# axiom_beta_interface_dummy_v0_13_r1_6.net
KiCad netlist of a schematic drawn in EAGLE
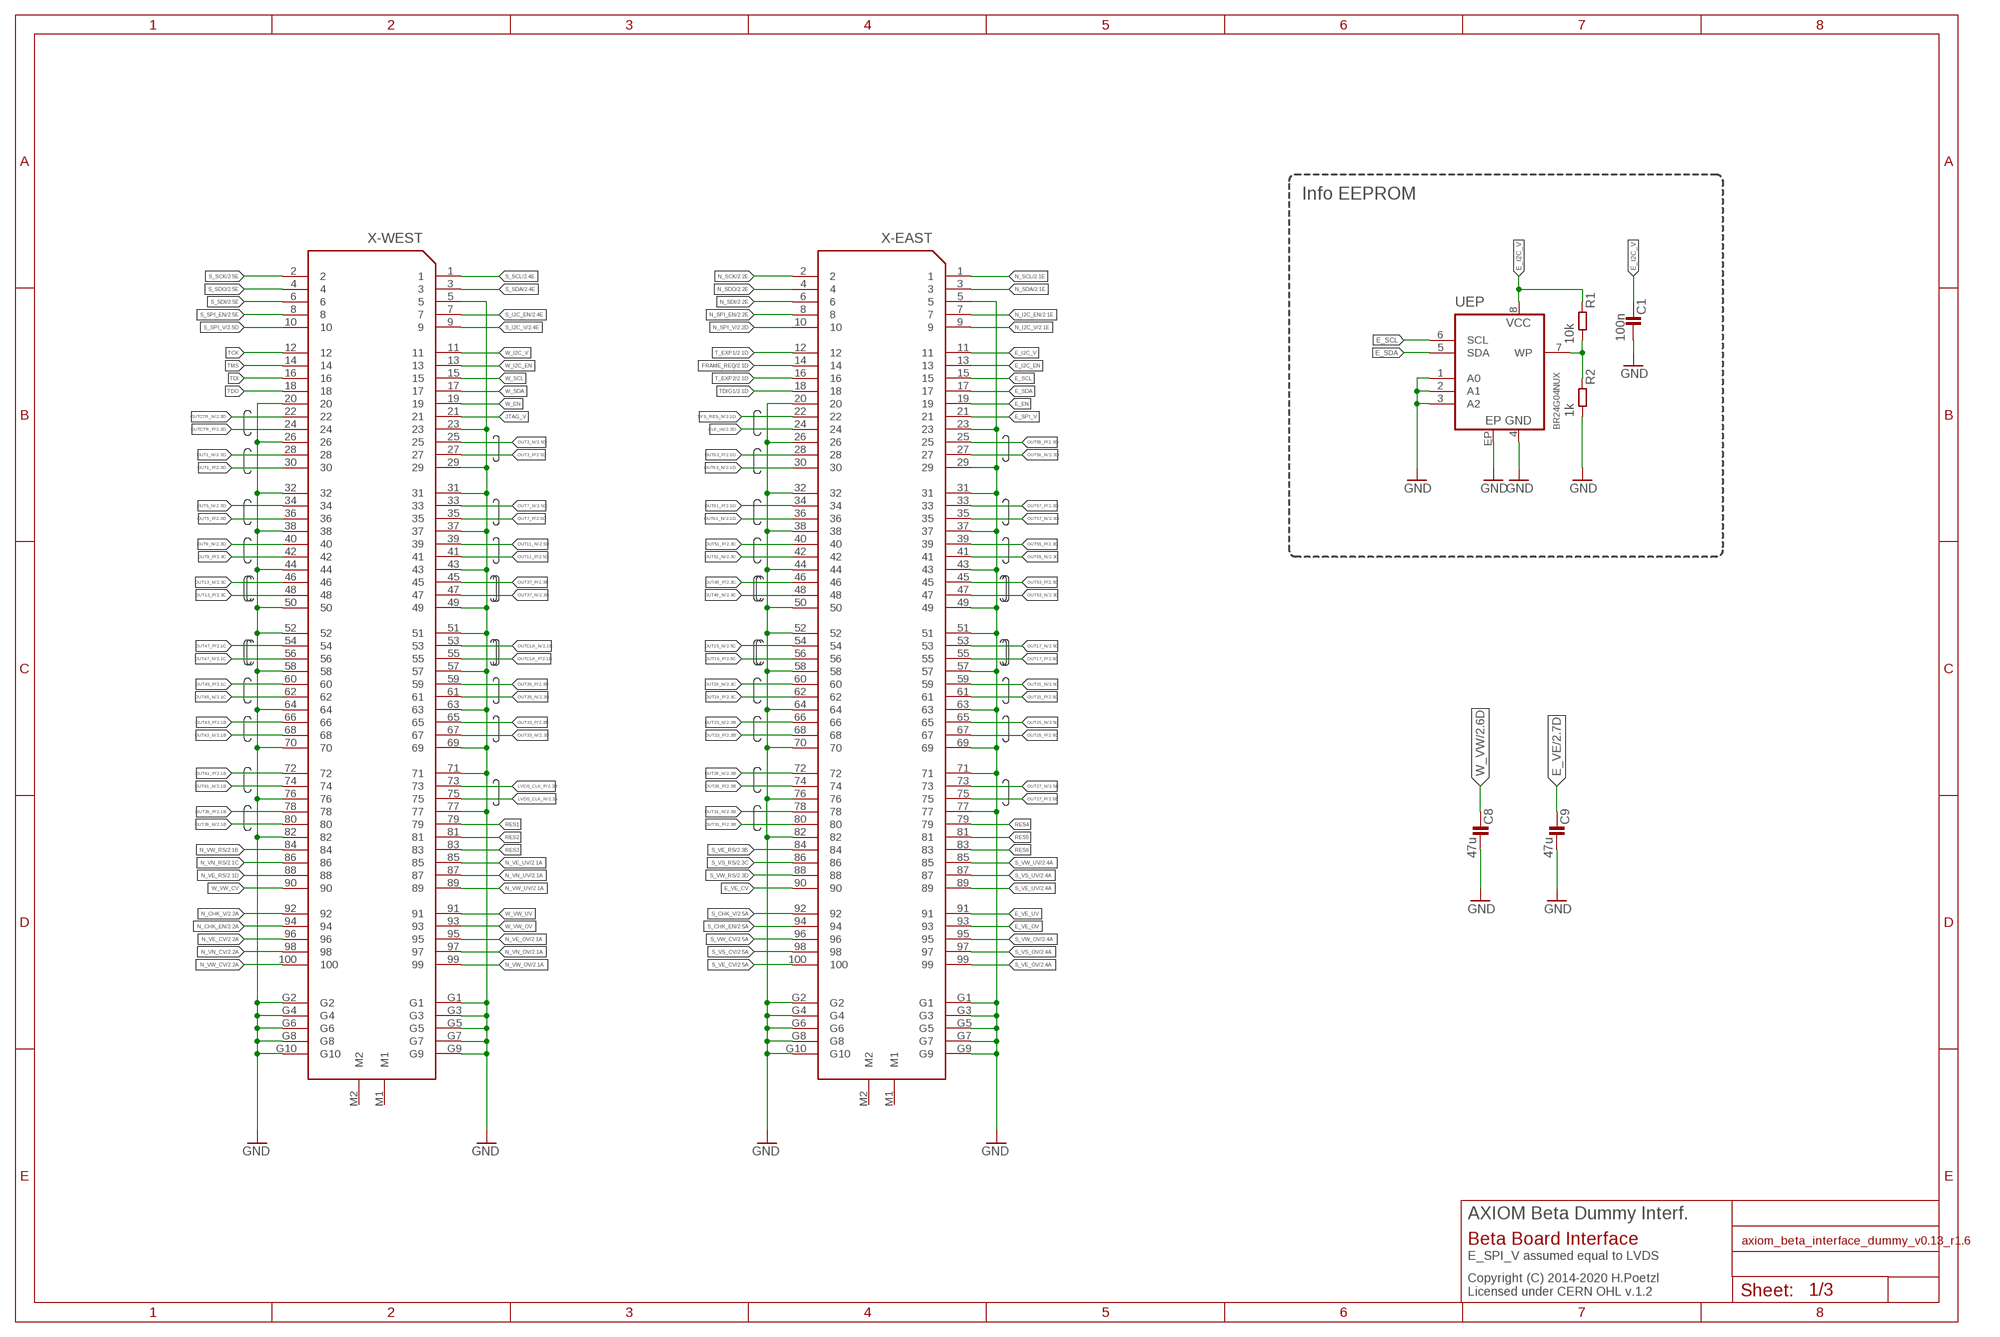
[diagram p0: schematic, sheet 1]
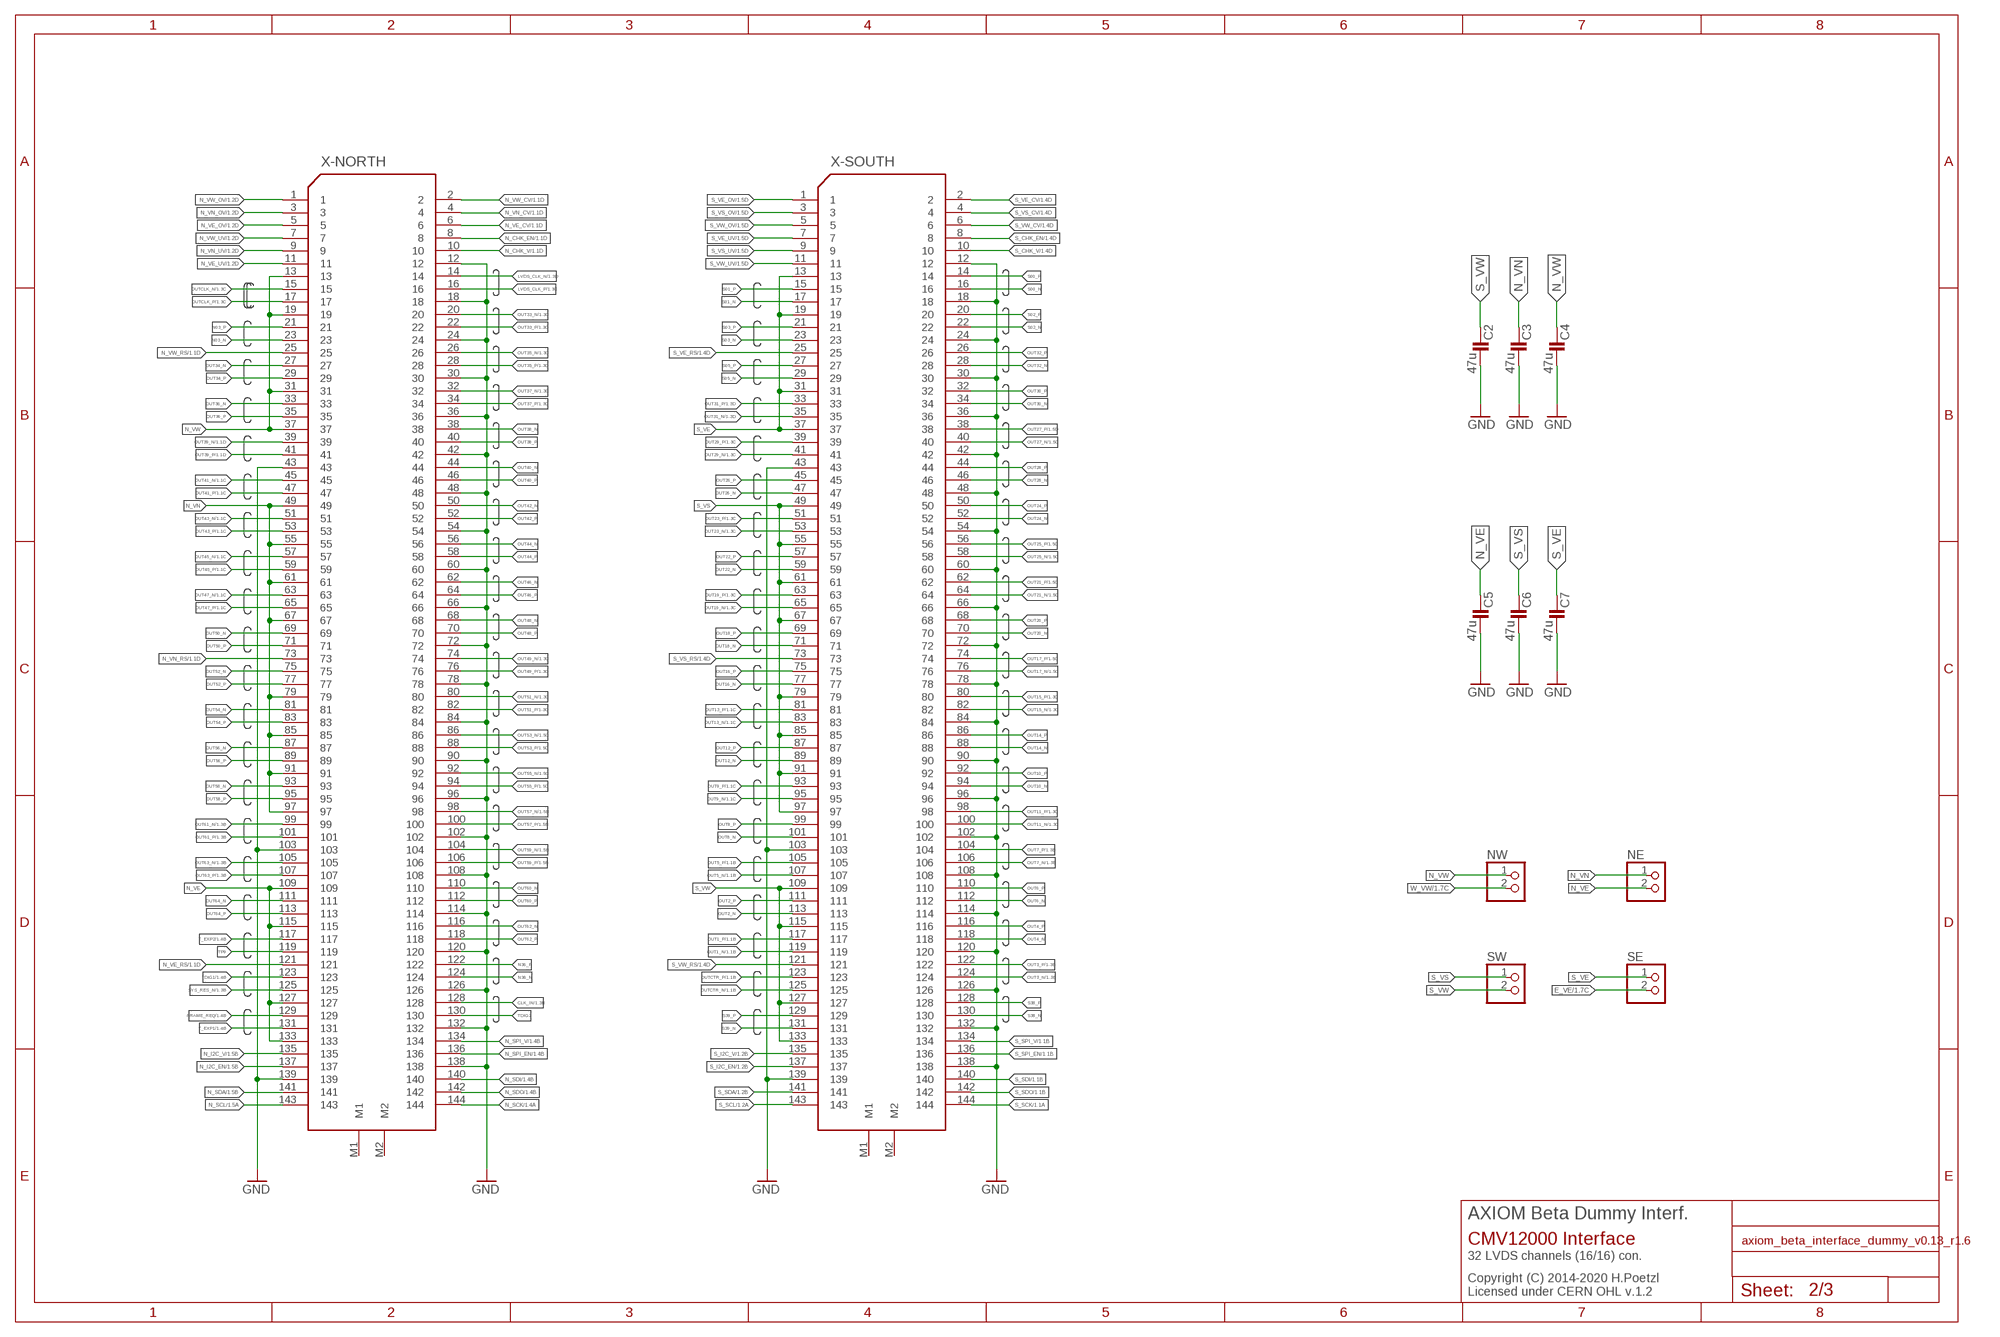
[diagram p1: schematic, sheet 2]
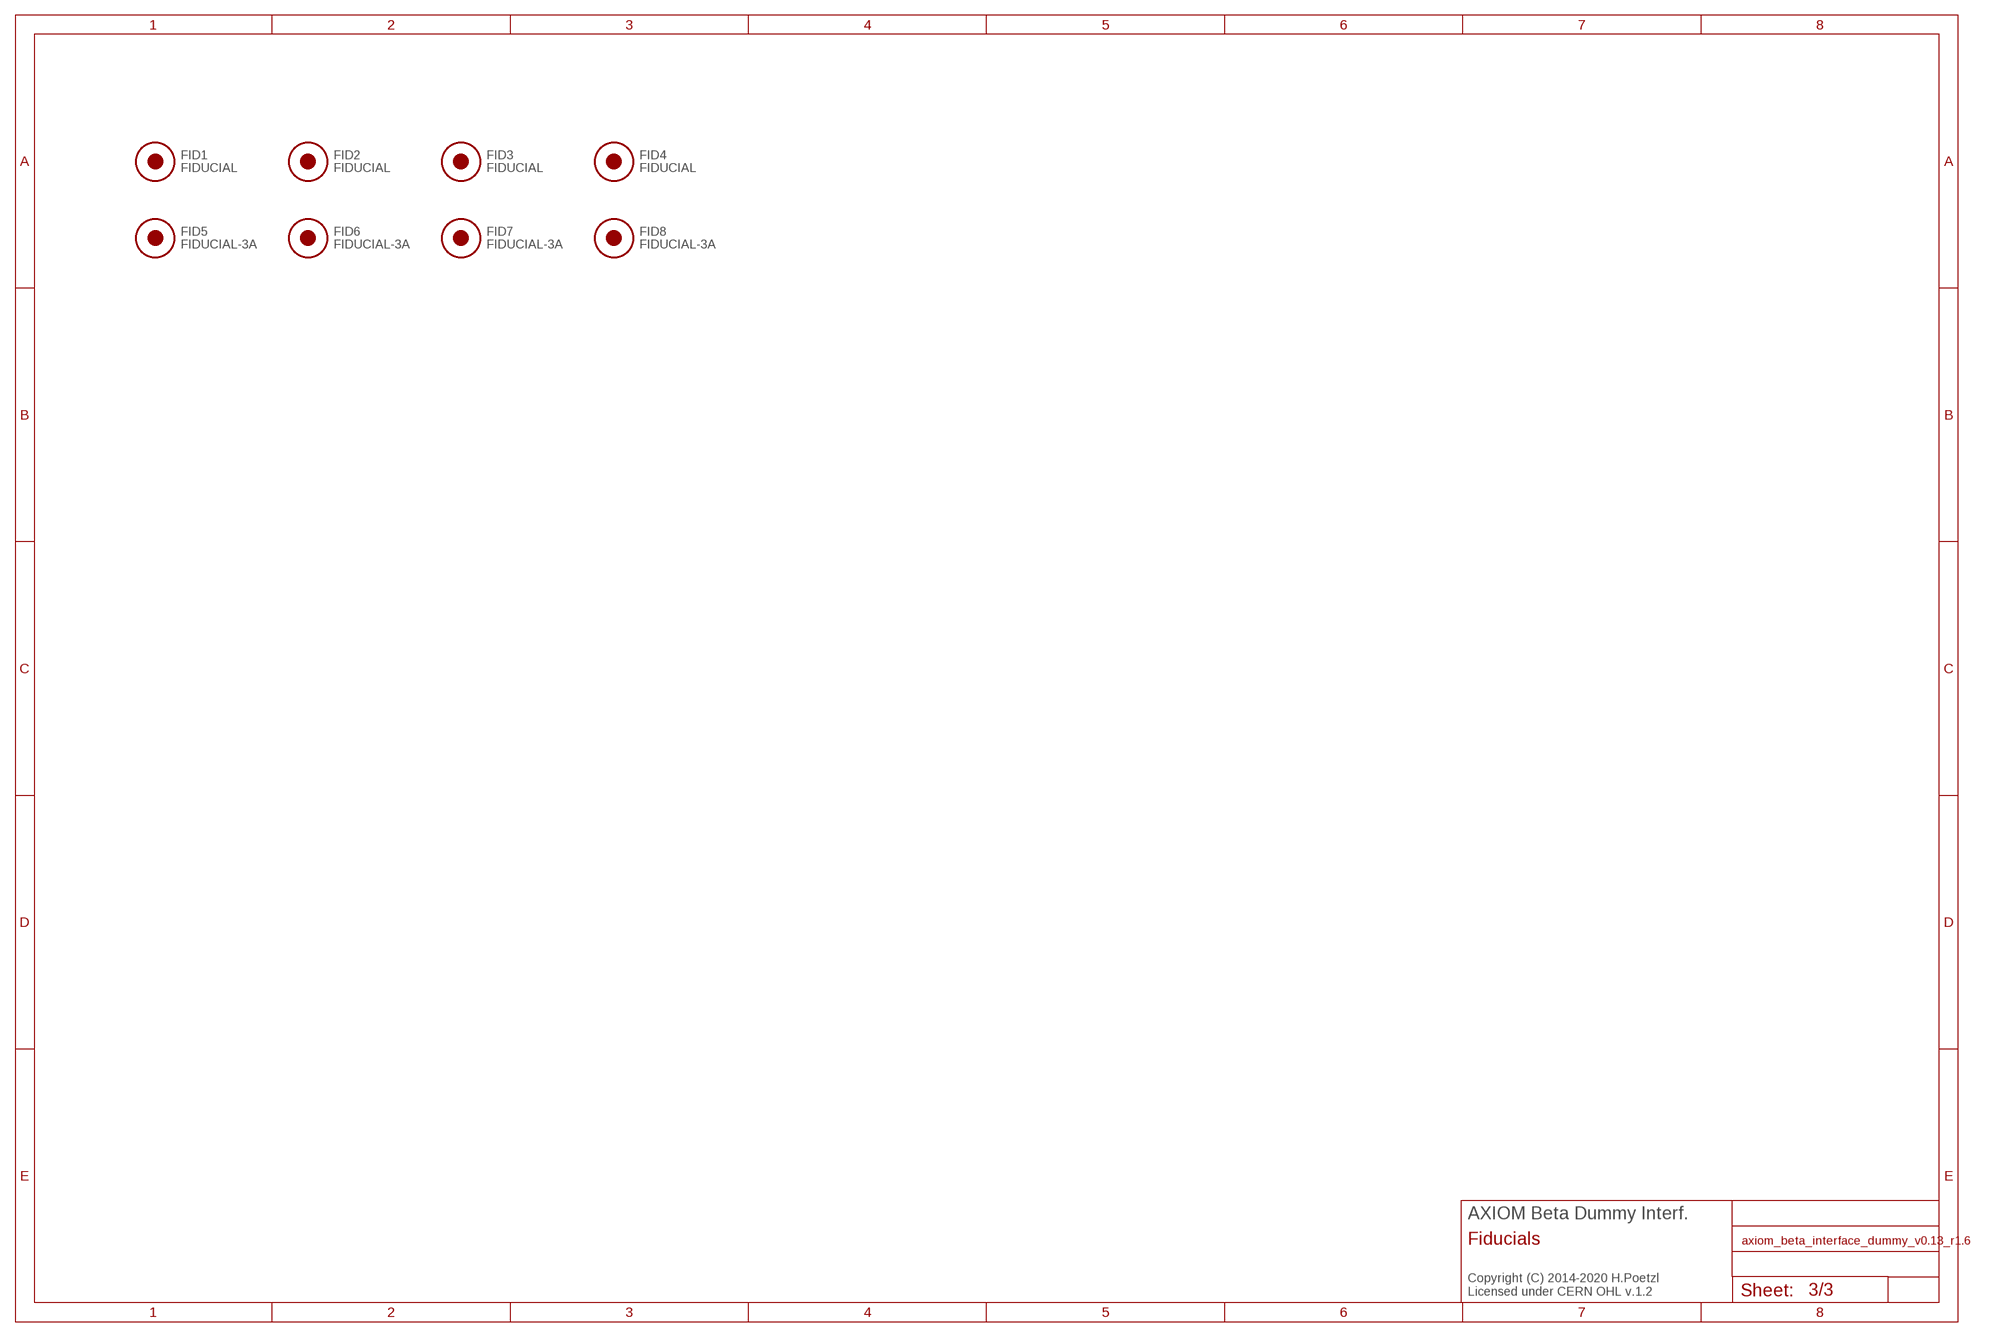
[diagram p2: schematic, sheet 3]

(export (version "E")
  (design (tool "Eeschema 10.0.6"))
  (components
    (comp (ref "C2")
      (value "47u")
      (footprint "eagle-import:0805-B")
      (libsource (lib "eagle-import") (part "C0805-B"))
    )
    (comp (ref "C3")
      (value "47u")
      (footprint "eagle-import:0805-B")
      (libsource (lib "eagle-import") (part "C0805-B"))
    )
    (comp (ref "C4")
      (value "47u")
      (footprint "eagle-import:0805-B")
      (libsource (lib "eagle-import") (part "C0805-B"))
    )
    (comp (ref "C5")
      (value "47u")
      (footprint "eagle-import:0805-B")
      (libsource (lib "eagle-import") (part "C0805-B"))
    )
    (comp (ref "C6")
      (value "47u")
      (footprint "eagle-import:0805-B")
      (libsource (lib "eagle-import") (part "C0805-B"))
    )
    (comp (ref "C7")
      (value "47u")
      (footprint "eagle-import:0805-B")
      (libsource (lib "eagle-import") (part "C0805-B"))
    )
    (comp (ref "NE")
      (value "PINHD-1X02_2.54")
      (footprint "eagle-import:1X02")
      (libsource (lib "eagle-import") (part "PINHD-1X02_2.54"))
    )
    (comp (ref "NW")
      (value "PINHD-1X02_2.54")
      (footprint "eagle-import:1X02")
      (libsource (lib "eagle-import") (part "PINHD-1X02_2.54"))
    )
    (comp (ref "SE")
      (value "PINHD-1X02_2.54")
      (footprint "eagle-import:1X02")
      (libsource (lib "eagle-import") (part "PINHD-1X02_2.54"))
    )
    (comp (ref "SW")
      (value "PINHD-1X02_2.54")
      (footprint "eagle-import:1X02")
      (libsource (lib "eagle-import") (part "PINHD-1X02_2.54"))
    )
    (comp (ref "X-NORTH")
      (value "FX10-144S")
      (footprint "eagle-import:FX10A-144S")
      (libsource (lib "eagle-import") (part "FX10-144S"))
    )
    (comp (ref "X-SOUTH")
      (value "FX10-144S")
      (footprint "eagle-import:FX10A-144S")
      (libsource (lib "eagle-import") (part "FX10-144S"))
    )
    (comp (ref "C1")
      (value "100n")
      (footprint "eagle-import:0402-B")
      (libsource (lib "eagle-import") (part "C0402-B"))
    )
    (comp (ref "C8")
      (value "47u")
      (footprint "eagle-import:0805-B")
      (libsource (lib "eagle-import") (part "C0805-B"))
    )
    (comp (ref "C9")
      (value "47u")
      (footprint "eagle-import:0805-B")
      (libsource (lib "eagle-import") (part "C0805-B"))
    )
    (comp (ref "R1")
      (value "10k")
      (footprint "eagle-import:0402-B")
      (libsource (lib "eagle-import") (part "R0402-B"))
    )
    (comp (ref "R2")
      (value "1k")
      (footprint "eagle-import:0402-B")
      (libsource (lib "eagle-import") (part "R0402-B"))
    )
    (comp (ref "UEP")
      (value "BR24G04NUX")
      (footprint "eagle-import:DFN200X300X100-9N")
      (libsource (lib "eagle-import") (part "BR24G04NUX"))
    )
    (comp (ref "X-EAST")
      (value "FX10-100/10P")
      (footprint "eagle-import:FX10A-100P_10")
      (libsource (lib "eagle-import") (part "FX10-100/10P"))
    )
    (comp (ref "X-WEST")
      (value "FX10-100/10P")
      (footprint "eagle-import:FX10A-100P_10")
      (libsource (lib "eagle-import") (part "FX10-100/10P"))
    )
    (comp (ref "FID1")
      (value "FIDUCIAL")
      (footprint "eagle-import:FID_ARROW")
      (libsource (lib "eagle-import") (part "FIDUCIAL"))
    )
    (comp (ref "FID2")
      (value "FIDUCIAL")
      (footprint "eagle-import:FID_ARROW")
      (libsource (lib "eagle-import") (part "FIDUCIAL"))
    )
    (comp (ref "FID3")
      (value "FIDUCIAL")
      (footprint "eagle-import:FID_ARROW")
      (libsource (lib "eagle-import") (part "FIDUCIAL"))
    )
    (comp (ref "FID4")
      (value "FIDUCIAL")
      (footprint "eagle-import:FID_ARROW")
      (libsource (lib "eagle-import") (part "FIDUCIAL"))
    )
    (comp (ref "FID5")
      (value "FIDUCIAL-3A")
      (footprint "eagle-import:FID_3ARROW")
      (libsource (lib "eagle-import") (part "FIDUCIAL-3A"))
    )
    (comp (ref "FID6")
      (value "FIDUCIAL-3A")
      (footprint "eagle-import:FID_3ARROW")
      (libsource (lib "eagle-import") (part "FIDUCIAL-3A"))
    )
    (comp (ref "FID7")
      (value "FIDUCIAL-3A")
      (footprint "eagle-import:FID_3ARROW")
      (libsource (lib "eagle-import") (part "FIDUCIAL-3A"))
    )
    (comp (ref "FID8")
      (value "FIDUCIAL-3A")
      (footprint "eagle-import:FID_3ARROW")
      (libsource (lib "eagle-import") (part "FIDUCIAL-3A"))
    )
  )
  (nets
    (net (code "1") (name "CLK_IN") (class "Default")
      (node (ref "X-EAST") (pin "24") (pinfunction "24_24") (pintype "bidirectional"))
      (node (ref "X-NORTH") (pin "128") (pinfunction "128_128") (pintype "bidirectional"))
    )
    (net (code "2") (name "E_EN") (class "Default")
      (node (ref "X-EAST") (pin "19") (pinfunction "19_19") (pintype "bidirectional"))
    )
    (net (code "3") (name "E_I2C_EN") (class "Default")
      (node (ref "X-EAST") (pin "13") (pinfunction "13_13") (pintype "bidirectional"))
    )
    (net (code "4") (name "E_I2C_V") (class "Default")
      (node (ref "C1") (pin "1") (pinfunction "1_1") (pintype "passive"))
      (node (ref "R1") (pin "1") (pinfunction "1_1") (pintype "passive"))
      (node (ref "UEP") (pin "8") (pinfunction "VCC_8") (pintype "power_in"))
      (node (ref "X-EAST") (pin "11") (pinfunction "11_11") (pintype "bidirectional"))
    )
    (net (code "5") (name "E_SCL") (class "Default")
      (node (ref "UEP") (pin "6") (pinfunction "SCL_6") (pintype "input"))
      (node (ref "X-EAST") (pin "15") (pinfunction "15_15") (pintype "bidirectional"))
    )
    (net (code "6") (name "E_SDA") (class "Default")
      (node (ref "UEP") (pin "5") (pinfunction "SDA_5") (pintype "bidirectional"))
      (node (ref "X-EAST") (pin "17") (pinfunction "17_17") (pintype "bidirectional"))
    )
    (net (code "7") (name "E_SPI_V") (class "Default")
      (node (ref "X-EAST") (pin "21") (pinfunction "21_21") (pintype "bidirectional"))
    )
    (net (code "8") (name "E_VE") (class "Default")
      (node (ref "C9") (pin "1") (pinfunction "1_1") (pintype "passive"))
      (node (ref "SE") (pin "2") (pinfunction "2_2") (pintype "passive"))
    )
    (net (code "9") (name "E_VE_CV") (class "Default")
      (node (ref "X-EAST") (pin "90") (pinfunction "90_90") (pintype "bidirectional"))
    )
    (net (code "10") (name "E_VE_OV") (class "Default")
      (node (ref "X-EAST") (pin "93") (pinfunction "93_93") (pintype "bidirectional"))
    )
    (net (code "11") (name "E_VE_UV") (class "Default")
      (node (ref "X-EAST") (pin "91") (pinfunction "91_91") (pintype "bidirectional"))
    )
    (net (code "12") (name "FRAME_REQ") (class "Default")
      (node (ref "X-EAST") (pin "14") (pinfunction "14_14") (pintype "bidirectional"))
      (node (ref "X-NORTH") (pin "129") (pinfunction "129_129") (pintype "bidirectional"))
    )
    (net (code "13") (name "GND") (class "Default")
      (node (ref "C1") (pin "2") (pinfunction "2_2") (pintype "passive"))
      (node (ref "C2") (pin "2") (pinfunction "2_2") (pintype "passive"))
      (node (ref "C3") (pin "2") (pinfunction "2_2") (pintype "passive"))
      (node (ref "C4") (pin "2") (pinfunction "2_2") (pintype "passive"))
      (node (ref "C5") (pin "2") (pinfunction "2_2") (pintype "passive"))
      (node (ref "C6") (pin "2") (pinfunction "2_2") (pintype "passive"))
      (node (ref "C7") (pin "2") (pinfunction "2_2") (pintype "passive"))
      (node (ref "C8") (pin "2") (pinfunction "2_2") (pintype "passive"))
      (node (ref "C9") (pin "2") (pinfunction "2_2") (pintype "passive"))
      (node (ref "R2") (pin "2") (pinfunction "2_2") (pintype "passive"))
      (node (ref "UEP") (pin "1") (pinfunction "A0_1") (pintype "input"))
      (node (ref "UEP") (pin "2") (pinfunction "A1_2") (pintype "input"))
      (node (ref "UEP") (pin "3") (pinfunction "A2_3") (pintype "input"))
      (node (ref "UEP") (pin "4") (pinfunction "GND_4") (pintype "passive"))
      (node (ref "UEP") (pin "EP") (pinfunction "EP_EP") (pintype "passive"))
      (node (ref "X-EAST") (pin "20") (pinfunction "20_20") (pintype "bidirectional"))
      (node (ref "X-EAST") (pin "23") (pinfunction "23_23") (pintype "bidirectional"))
      (node (ref "X-EAST") (pin "26") (pinfunction "26_26") (pintype "bidirectional"))
      (node (ref "X-EAST") (pin "29") (pinfunction "29_29") (pintype "bidirectional"))
      (node (ref "X-EAST") (pin "31") (pinfunction "31_31") (pintype "bidirectional"))
      (node (ref "X-EAST") (pin "32") (pinfunction "32_32") (pintype "bidirectional"))
      (node (ref "X-EAST") (pin "37") (pinfunction "37_37") (pintype "bidirectional"))
      (node (ref "X-EAST") (pin "38") (pinfunction "38_38") (pintype "bidirectional"))
      (node (ref "X-EAST") (pin "43") (pinfunction "43_43") (pintype "bidirectional"))
      (node (ref "X-EAST") (pin "44") (pinfunction "44_44") (pintype "bidirectional"))
      (node (ref "X-EAST") (pin "49") (pinfunction "49_49") (pintype "bidirectional"))
      (node (ref "X-EAST") (pin "5") (pinfunction "5_5") (pintype "bidirectional"))
      (node (ref "X-EAST") (pin "50") (pinfunction "50_50") (pintype "bidirectional"))
      (node (ref "X-EAST") (pin "51") (pinfunction "51_51") (pintype "bidirectional"))
      (node (ref "X-EAST") (pin "52") (pinfunction "52_52") (pintype "bidirectional"))
      (node (ref "X-EAST") (pin "57") (pinfunction "57_57") (pintype "bidirectional"))
      (node (ref "X-EAST") (pin "58") (pinfunction "58_58") (pintype "bidirectional"))
      (node (ref "X-EAST") (pin "63") (pinfunction "63_63") (pintype "bidirectional"))
      (node (ref "X-EAST") (pin "64") (pinfunction "64_64") (pintype "bidirectional"))
      (node (ref "X-EAST") (pin "69") (pinfunction "69_69") (pintype "bidirectional"))
      (node (ref "X-EAST") (pin "70") (pinfunction "70_70") (pintype "bidirectional"))
      (node (ref "X-EAST") (pin "71") (pinfunction "71_71") (pintype "bidirectional"))
      (node (ref "X-EAST") (pin "76") (pinfunction "76_76") (pintype "bidirectional"))
      (node (ref "X-EAST") (pin "77") (pinfunction "77_77") (pintype "bidirectional"))
      (node (ref "X-EAST") (pin "82") (pinfunction "82_82") (pintype "bidirectional"))
      (node (ref "X-EAST") (pin "G1") (pinfunction "G1_G1") (pintype "bidirectional"))
      (node (ref "X-EAST") (pin "G10") (pinfunction "G10_G10") (pintype "bidirectional"))
      (node (ref "X-EAST") (pin "G2") (pinfunction "G2_G2") (pintype "bidirectional"))
      (node (ref "X-EAST") (pin "G3") (pinfunction "G3_G3") (pintype "bidirectional"))
      (node (ref "X-EAST") (pin "G4") (pinfunction "G4_G4") (pintype "bidirectional"))
      (node (ref "X-EAST") (pin "G5") (pinfunction "G5_G5") (pintype "bidirectional"))
      (node (ref "X-EAST") (pin "G6") (pinfunction "G6_G6") (pintype "bidirectional"))
      (node (ref "X-EAST") (pin "G7") (pinfunction "G7_G7") (pintype "bidirectional"))
      (node (ref "X-EAST") (pin "G8") (pinfunction "G8_G8") (pintype "bidirectional"))
      (node (ref "X-EAST") (pin "G9") (pinfunction "G9_G9") (pintype "bidirectional"))
      (node (ref "X-NORTH") (pin "102") (pinfunction "102_102") (pintype "bidirectional"))
      (node (ref "X-NORTH") (pin "103") (pinfunction "103_103") (pintype "bidirectional"))
      (node (ref "X-NORTH") (pin "108") (pinfunction "108_108") (pintype "bidirectional"))
      (node (ref "X-NORTH") (pin "114") (pinfunction "114_114") (pintype "bidirectional"))
      (node (ref "X-NORTH") (pin "12") (pinfunction "12_12") (pintype "bidirectional"))
      (node (ref "X-NORTH") (pin "120") (pinfunction "120_120") (pintype "bidirectional"))
      (node (ref "X-NORTH") (pin "126") (pinfunction "126_126") (pintype "bidirectional"))
      (node (ref "X-NORTH") (pin "132") (pinfunction "132_132") (pintype "bidirectional"))
      (node (ref "X-NORTH") (pin "138") (pinfunction "138_138") (pintype "bidirectional"))
      (node (ref "X-NORTH") (pin "139") (pinfunction "139_139") (pintype "bidirectional"))
      (node (ref "X-NORTH") (pin "18") (pinfunction "18_18") (pintype "bidirectional"))
      (node (ref "X-NORTH") (pin "24") (pinfunction "24_24") (pintype "bidirectional"))
      (node (ref "X-NORTH") (pin "30") (pinfunction "30_30") (pintype "bidirectional"))
      (node (ref "X-NORTH") (pin "36") (pinfunction "36_36") (pintype "bidirectional"))
      (node (ref "X-NORTH") (pin "42") (pinfunction "42_42") (pintype "bidirectional"))
      (node (ref "X-NORTH") (pin "43") (pinfunction "43_43") (pintype "bidirectional"))
      (node (ref "X-NORTH") (pin "48") (pinfunction "48_48") (pintype "bidirectional"))
      (node (ref "X-NORTH") (pin "54") (pinfunction "54_54") (pintype "bidirectional"))
      (node (ref "X-NORTH") (pin "60") (pinfunction "60_60") (pintype "bidirectional"))
      (node (ref "X-NORTH") (pin "66") (pinfunction "66_66") (pintype "bidirectional"))
      (node (ref "X-NORTH") (pin "72") (pinfunction "72_72") (pintype "bidirectional"))
      (node (ref "X-NORTH") (pin "78") (pinfunction "78_78") (pintype "bidirectional"))
      (node (ref "X-NORTH") (pin "84") (pinfunction "84_84") (pintype "bidirectional"))
      (node (ref "X-NORTH") (pin "90") (pinfunction "90_90") (pintype "bidirectional"))
      (node (ref "X-NORTH") (pin "96") (pinfunction "96_96") (pintype "bidirectional"))
      (node (ref "X-SOUTH") (pin "102") (pinfunction "102_102") (pintype "bidirectional"))
      (node (ref "X-SOUTH") (pin "103") (pinfunction "103_103") (pintype "bidirectional"))
      (node (ref "X-SOUTH") (pin "108") (pinfunction "108_108") (pintype "bidirectional"))
      (node (ref "X-SOUTH") (pin "114") (pinfunction "114_114") (pintype "bidirectional"))
      (node (ref "X-SOUTH") (pin "12") (pinfunction "12_12") (pintype "bidirectional"))
      (node (ref "X-SOUTH") (pin "120") (pinfunction "120_120") (pintype "bidirectional"))
      (node (ref "X-SOUTH") (pin "126") (pinfunction "126_126") (pintype "bidirectional"))
      (node (ref "X-SOUTH") (pin "132") (pinfunction "132_132") (pintype "bidirectional"))
      (node (ref "X-SOUTH") (pin "138") (pinfunction "138_138") (pintype "bidirectional"))
      (node (ref "X-SOUTH") (pin "139") (pinfunction "139_139") (pintype "bidirectional"))
      (node (ref "X-SOUTH") (pin "18") (pinfunction "18_18") (pintype "bidirectional"))
      (node (ref "X-SOUTH") (pin "24") (pinfunction "24_24") (pintype "bidirectional"))
      (node (ref "X-SOUTH") (pin "30") (pinfunction "30_30") (pintype "bidirectional"))
      (node (ref "X-SOUTH") (pin "36") (pinfunction "36_36") (pintype "bidirectional"))
      (node (ref "X-SOUTH") (pin "42") (pinfunction "42_42") (pintype "bidirectional"))
      (node (ref "X-SOUTH") (pin "43") (pinfunction "43_43") (pintype "bidirectional"))
      (node (ref "X-SOUTH") (pin "48") (pinfunction "48_48") (pintype "bidirectional"))
      (node (ref "X-SOUTH") (pin "54") (pinfunction "54_54") (pintype "bidirectional"))
      (node (ref "X-SOUTH") (pin "60") (pinfunction "60_60") (pintype "bidirectional"))
      (node (ref "X-SOUTH") (pin "66") (pinfunction "66_66") (pintype "bidirectional"))
      (node (ref "X-SOUTH") (pin "72") (pinfunction "72_72") (pintype "bidirectional"))
      (node (ref "X-SOUTH") (pin "78") (pinfunction "78_78") (pintype "bidirectional"))
      (node (ref "X-SOUTH") (pin "84") (pinfunction "84_84") (pintype "bidirectional"))
      (node (ref "X-SOUTH") (pin "90") (pinfunction "90_90") (pintype "bidirectional"))
      (node (ref "X-SOUTH") (pin "96") (pinfunction "96_96") (pintype "bidirectional"))
      (node (ref "X-WEST") (pin "20") (pinfunction "20_20") (pintype "bidirectional"))
      (node (ref "X-WEST") (pin "23") (pinfunction "23_23") (pintype "bidirectional"))
      (node (ref "X-WEST") (pin "26") (pinfunction "26_26") (pintype "bidirectional"))
      (node (ref "X-WEST") (pin "29") (pinfunction "29_29") (pintype "bidirectional"))
      (node (ref "X-WEST") (pin "31") (pinfunction "31_31") (pintype "bidirectional"))
      (node (ref "X-WEST") (pin "32") (pinfunction "32_32") (pintype "bidirectional"))
      (node (ref "X-WEST") (pin "37") (pinfunction "37_37") (pintype "bidirectional"))
      (node (ref "X-WEST") (pin "38") (pinfunction "38_38") (pintype "bidirectional"))
      (node (ref "X-WEST") (pin "43") (pinfunction "43_43") (pintype "bidirectional"))
      (node (ref "X-WEST") (pin "44") (pinfunction "44_44") (pintype "bidirectional"))
      (node (ref "X-WEST") (pin "49") (pinfunction "49_49") (pintype "bidirectional"))
      (node (ref "X-WEST") (pin "5") (pinfunction "5_5") (pintype "bidirectional"))
      (node (ref "X-WEST") (pin "50") (pinfunction "50_50") (pintype "bidirectional"))
      (node (ref "X-WEST") (pin "51") (pinfunction "51_51") (pintype "bidirectional"))
      (node (ref "X-WEST") (pin "52") (pinfunction "52_52") (pintype "bidirectional"))
      (node (ref "X-WEST") (pin "57") (pinfunction "57_57") (pintype "bidirectional"))
      (node (ref "X-WEST") (pin "58") (pinfunction "58_58") (pintype "bidirectional"))
      (node (ref "X-WEST") (pin "63") (pinfunction "63_63") (pintype "bidirectional"))
      (node (ref "X-WEST") (pin "64") (pinfunction "64_64") (pintype "bidirectional"))
      (node (ref "X-WEST") (pin "69") (pinfunction "69_69") (pintype "bidirectional"))
      (node (ref "X-WEST") (pin "70") (pinfunction "70_70") (pintype "bidirectional"))
      (node (ref "X-WEST") (pin "71") (pinfunction "71_71") (pintype "bidirectional"))
      (node (ref "X-WEST") (pin "76") (pinfunction "76_76") (pintype "bidirectional"))
      (node (ref "X-WEST") (pin "77") (pinfunction "77_77") (pintype "bidirectional"))
      (node (ref "X-WEST") (pin "82") (pinfunction "82_82") (pintype "bidirectional"))
      (node (ref "X-WEST") (pin "G1") (pinfunction "G1_G1") (pintype "bidirectional"))
      (node (ref "X-WEST") (pin "G10") (pinfunction "G10_G10") (pintype "bidirectional"))
      (node (ref "X-WEST") (pin "G2") (pinfunction "G2_G2") (pintype "bidirectional"))
      (node (ref "X-WEST") (pin "G3") (pinfunction "G3_G3") (pintype "bidirectional"))
      (node (ref "X-WEST") (pin "G4") (pinfunction "G4_G4") (pintype "bidirectional"))
      (node (ref "X-WEST") (pin "G5") (pinfunction "G5_G5") (pintype "bidirectional"))
      (node (ref "X-WEST") (pin "G6") (pinfunction "G6_G6") (pintype "bidirectional"))
      (node (ref "X-WEST") (pin "G7") (pinfunction "G7_G7") (pintype "bidirectional"))
      (node (ref "X-WEST") (pin "G8") (pinfunction "G8_G8") (pintype "bidirectional"))
      (node (ref "X-WEST") (pin "G9") (pinfunction "G9_G9") (pintype "bidirectional"))
    )
    (net (code "14") (name "JTAG_V") (class "Default")
      (node (ref "X-WEST") (pin "21") (pinfunction "21_21") (pintype "bidirectional"))
    )
    (net (code "15") (name "LVDS_CLK_N") (class "Default")
      (node (ref "X-NORTH") (pin "14") (pinfunction "14_14") (pintype "bidirectional"))
      (node (ref "X-WEST") (pin "75") (pinfunction "75_75") (pintype "bidirectional"))
    )
    (net (code "16") (name "LVDS_CLK_P") (class "Default")
      (node (ref "X-NORTH") (pin "16") (pinfunction "16_16") (pintype "bidirectional"))
      (node (ref "X-WEST") (pin "73") (pinfunction "73_73") (pintype "bidirectional"))
    )
    (net (code "17") (name "N03_N") (class "Default")
      (node (ref "X-NORTH") (pin "23") (pinfunction "23_23") (pintype "bidirectional"))
    )
    (net (code "18") (name "N03_P") (class "Default")
      (node (ref "X-NORTH") (pin "21") (pinfunction "21_21") (pintype "bidirectional"))
    )
    (net (code "19") (name "N36_N") (class "Default")
      (node (ref "X-NORTH") (pin "124") (pinfunction "124_124") (pintype "bidirectional"))
    )
    (net (code "20") (name "N36_P") (class "Default")
      (node (ref "X-NORTH") (pin "122") (pinfunction "122_122") (pintype "bidirectional"))
    )
    (net (code "21") (name "N_CHK_EN") (class "Default")
      (node (ref "X-NORTH") (pin "8") (pinfunction "8_8") (pintype "bidirectional"))
      (node (ref "X-WEST") (pin "94") (pinfunction "94_94") (pintype "bidirectional"))
    )
    (net (code "22") (name "N_CHK_V") (class "Default")
      (node (ref "X-NORTH") (pin "10") (pinfunction "10_10") (pintype "bidirectional"))
      (node (ref "X-WEST") (pin "92") (pinfunction "92_92") (pintype "bidirectional"))
    )
    (net (code "23") (name "N_I2C_EN") (class "Default")
      (node (ref "X-EAST") (pin "7") (pinfunction "7_7") (pintype "bidirectional"))
      (node (ref "X-NORTH") (pin "137") (pinfunction "137_137") (pintype "bidirectional"))
    )
    (net (code "24") (name "N_I2C_V") (class "Default")
      (node (ref "X-EAST") (pin "9") (pinfunction "9_9") (pintype "bidirectional"))
      (node (ref "X-NORTH") (pin "135") (pinfunction "135_135") (pintype "bidirectional"))
    )
    (net (code "25") (name "N_SCK") (class "Default")
      (node (ref "X-EAST") (pin "2") (pinfunction "2_2") (pintype "bidirectional"))
      (node (ref "X-NORTH") (pin "144") (pinfunction "144_144") (pintype "bidirectional"))
    )
    (net (code "26") (name "N_SCL") (class "Default")
      (node (ref "X-EAST") (pin "1") (pinfunction "1_1") (pintype "bidirectional"))
      (node (ref "X-NORTH") (pin "143") (pinfunction "143_143") (pintype "bidirectional"))
    )
    (net (code "27") (name "N_SDA") (class "Default")
      (node (ref "X-EAST") (pin "3") (pinfunction "3_3") (pintype "bidirectional"))
      (node (ref "X-NORTH") (pin "141") (pinfunction "141_141") (pintype "bidirectional"))
    )
    (net (code "28") (name "N_SDI") (class "Default")
      (node (ref "X-EAST") (pin "6") (pinfunction "6_6") (pintype "bidirectional"))
      (node (ref "X-NORTH") (pin "140") (pinfunction "140_140") (pintype "bidirectional"))
    )
    (net (code "29") (name "N_SDO") (class "Default")
      (node (ref "X-EAST") (pin "4") (pinfunction "4_4") (pintype "bidirectional"))
      (node (ref "X-NORTH") (pin "142") (pinfunction "142_142") (pintype "bidirectional"))
    )
    (net (code "30") (name "N_SPI_EN") (class "Default")
      (node (ref "X-EAST") (pin "8") (pinfunction "8_8") (pintype "bidirectional"))
      (node (ref "X-NORTH") (pin "136") (pinfunction "136_136") (pintype "bidirectional"))
    )
    (net (code "31") (name "N_SPI_V") (class "Default")
      (node (ref "X-EAST") (pin "10") (pinfunction "10_10") (pintype "bidirectional"))
      (node (ref "X-NORTH") (pin "134") (pinfunction "134_134") (pintype "bidirectional"))
    )
    (net (code "32") (name "N_VE") (class "Default")
      (node (ref "C5") (pin "1") (pinfunction "1_1") (pintype "passive"))
      (node (ref "NE") (pin "2") (pinfunction "2_2") (pintype "passive"))
      (node (ref "X-NORTH") (pin "109") (pinfunction "109_109") (pintype "bidirectional"))
      (node (ref "X-NORTH") (pin "115") (pinfunction "115_115") (pintype "bidirectional"))
      (node (ref "X-NORTH") (pin "127") (pinfunction "127_127") (pintype "bidirectional"))
      (node (ref "X-NORTH") (pin "133") (pinfunction "133_133") (pintype "bidirectional"))
    )
    (net (code "33") (name "N_VE_CV") (class "Default")
      (node (ref "X-NORTH") (pin "6") (pinfunction "6_6") (pintype "bidirectional"))
      (node (ref "X-WEST") (pin "96") (pinfunction "96_96") (pintype "bidirectional"))
    )
    (net (code "34") (name "N_VE_OV") (class "Default")
      (node (ref "X-NORTH") (pin "5") (pinfunction "5_5") (pintype "bidirectional"))
      (node (ref "X-WEST") (pin "95") (pinfunction "95_95") (pintype "bidirectional"))
    )
    (net (code "35") (name "N_VE_RS") (class "Default")
      (node (ref "X-NORTH") (pin "121") (pinfunction "121_121") (pintype "bidirectional"))
      (node (ref "X-WEST") (pin "88") (pinfunction "88_88") (pintype "bidirectional"))
    )
    (net (code "36") (name "N_VE_UV") (class "Default")
      (node (ref "X-NORTH") (pin "11") (pinfunction "11_11") (pintype "bidirectional"))
      (node (ref "X-WEST") (pin "85") (pinfunction "85_85") (pintype "bidirectional"))
    )
    (net (code "37") (name "N_VN") (class "Default")
      (node (ref "C3") (pin "1") (pinfunction "1_1") (pintype "passive"))
      (node (ref "NE") (pin "1") (pinfunction "1_1") (pintype "passive"))
      (node (ref "X-NORTH") (pin "49") (pinfunction "49_49") (pintype "bidirectional"))
      (node (ref "X-NORTH") (pin "55") (pinfunction "55_55") (pintype "bidirectional"))
      (node (ref "X-NORTH") (pin "61") (pinfunction "61_61") (pintype "bidirectional"))
      (node (ref "X-NORTH") (pin "67") (pinfunction "67_67") (pintype "bidirectional"))
      (node (ref "X-NORTH") (pin "79") (pinfunction "79_79") (pintype "bidirectional"))
      (node (ref "X-NORTH") (pin "85") (pinfunction "85_85") (pintype "bidirectional"))
      (node (ref "X-NORTH") (pin "91") (pinfunction "91_91") (pintype "bidirectional"))
      (node (ref "X-NORTH") (pin "97") (pinfunction "97_97") (pintype "bidirectional"))
    )
    (net (code "38") (name "N_VN_CV") (class "Default")
      (node (ref "X-NORTH") (pin "4") (pinfunction "4_4") (pintype "bidirectional"))
      (node (ref "X-WEST") (pin "98") (pinfunction "98_98") (pintype "bidirectional"))
    )
    (net (code "39") (name "N_VN_OV") (class "Default")
      (node (ref "X-NORTH") (pin "3") (pinfunction "3_3") (pintype "bidirectional"))
      (node (ref "X-WEST") (pin "97") (pinfunction "97_97") (pintype "bidirectional"))
    )
    (net (code "40") (name "N_VN_RS") (class "Default")
      (node (ref "X-NORTH") (pin "73") (pinfunction "73_73") (pintype "bidirectional"))
      (node (ref "X-WEST") (pin "86") (pinfunction "86_86") (pintype "bidirectional"))
    )
    (net (code "41") (name "N_VN_UV") (class "Default")
      (node (ref "X-NORTH") (pin "9") (pinfunction "9_9") (pintype "bidirectional"))
      (node (ref "X-WEST") (pin "87") (pinfunction "87_87") (pintype "bidirectional"))
    )
    (net (code "42") (name "N_VW") (class "Default")
      (node (ref "C4") (pin "1") (pinfunction "1_1") (pintype "passive"))
      (node (ref "NW") (pin "1") (pinfunction "1_1") (pintype "passive"))
      (node (ref "X-NORTH") (pin "13") (pinfunction "13_13") (pintype "bidirectional"))
      (node (ref "X-NORTH") (pin "19") (pinfunction "19_19") (pintype "bidirectional"))
      (node (ref "X-NORTH") (pin "31") (pinfunction "31_31") (pintype "bidirectional"))
      (node (ref "X-NORTH") (pin "37") (pinfunction "37_37") (pintype "bidirectional"))
    )
    (net (code "43") (name "N_VW_CV") (class "Default")
      (node (ref "X-NORTH") (pin "2") (pinfunction "2_2") (pintype "bidirectional"))
      (node (ref "X-WEST") (pin "100") (pinfunction "100_100") (pintype "bidirectional"))
    )
    (net (code "44") (name "N_VW_OV") (class "Default")
      (node (ref "X-NORTH") (pin "1") (pinfunction "1_1") (pintype "bidirectional"))
      (node (ref "X-WEST") (pin "99") (pinfunction "99_99") (pintype "bidirectional"))
    )
    (net (code "45") (name "N_VW_RS") (class "Default")
      (node (ref "X-NORTH") (pin "25") (pinfunction "25_25") (pintype "bidirectional"))
      (node (ref "X-WEST") (pin "84") (pinfunction "84_84") (pintype "bidirectional"))
    )
    (net (code "46") (name "N_VW_UV") (class "Default")
      (node (ref "X-NORTH") (pin "7") (pinfunction "7_7") (pintype "bidirectional"))
      (node (ref "X-WEST") (pin "89") (pinfunction "89_89") (pintype "bidirectional"))
    )
    (net (code "47") (name "Net-(UEP-WP)") (class "Default")
      (node (ref "R1") (pin "2") (pinfunction "2_2") (pintype "passive"))
      (node (ref "R2") (pin "1") (pinfunction "1_1") (pintype "passive"))
      (node (ref "UEP") (pin "7") (pinfunction "WP_7") (pintype "input"))
    )
    (net (code "48") (name "OUT1_N") (class "Default")
      (node (ref "X-SOUTH") (pin "119") (pinfunction "119_119") (pintype "bidirectional"))
      (node (ref "X-WEST") (pin "28") (pinfunction "28_28") (pintype "bidirectional"))
    )
    (net (code "49") (name "OUT1_P") (class "Default")
      (node (ref "X-SOUTH") (pin "117") (pinfunction "117_117") (pintype "bidirectional"))
      (node (ref "X-WEST") (pin "30") (pinfunction "30_30") (pintype "bidirectional"))
    )
    (net (code "50") (name "OUT2_N") (class "Default")
      (node (ref "X-SOUTH") (pin "113") (pinfunction "113_113") (pintype "bidirectional"))
    )
    (net (code "51") (name "OUT2_P") (class "Default")
      (node (ref "X-SOUTH") (pin "111") (pinfunction "111_111") (pintype "bidirectional"))
    )
    (net (code "52") (name "OUT3_N") (class "Default")
      (node (ref "X-SOUTH") (pin "124") (pinfunction "124_124") (pintype "bidirectional"))
      (node (ref "X-WEST") (pin "25") (pinfunction "25_25") (pintype "bidirectional"))
    )
    (net (code "53") (name "OUT3_P") (class "Default")
      (node (ref "X-SOUTH") (pin "122") (pinfunction "122_122") (pintype "bidirectional"))
      (node (ref "X-WEST") (pin "27") (pinfunction "27_27") (pintype "bidirectional"))
    )
    (net (code "54") (name "OUT4_N") (class "Default")
      (node (ref "X-SOUTH") (pin "118") (pinfunction "118_118") (pintype "bidirectional"))
    )
    (net (code "55") (name "OUT4_P") (class "Default")
      (node (ref "X-SOUTH") (pin "116") (pinfunction "116_116") (pintype "bidirectional"))
    )
    (net (code "56") (name "OUT5_N") (class "Default")
      (node (ref "X-SOUTH") (pin "107") (pinfunction "107_107") (pintype "bidirectional"))
      (node (ref "X-WEST") (pin "34") (pinfunction "34_34") (pintype "bidirectional"))
    )
    (net (code "57") (name "OUT5_P") (class "Default")
      (node (ref "X-SOUTH") (pin "105") (pinfunction "105_105") (pintype "bidirectional"))
      (node (ref "X-WEST") (pin "36") (pinfunction "36_36") (pintype "bidirectional"))
    )
    (net (code "58") (name "OUT6_N") (class "Default")
      (node (ref "X-SOUTH") (pin "112") (pinfunction "112_112") (pintype "bidirectional"))
    )
    (net (code "59") (name "OUT6_P") (class "Default")
      (node (ref "X-SOUTH") (pin "110") (pinfunction "110_110") (pintype "bidirectional"))
    )
    (net (code "60") (name "OUT7_N") (class "Default")
      (node (ref "X-SOUTH") (pin "106") (pinfunction "106_106") (pintype "bidirectional"))
      (node (ref "X-WEST") (pin "33") (pinfunction "33_33") (pintype "bidirectional"))
    )
    (net (code "61") (name "OUT7_P") (class "Default")
      (node (ref "X-SOUTH") (pin "104") (pinfunction "104_104") (pintype "bidirectional"))
      (node (ref "X-WEST") (pin "35") (pinfunction "35_35") (pintype "bidirectional"))
    )
    (net (code "62") (name "OUT8_N") (class "Default")
      (node (ref "X-SOUTH") (pin "101") (pinfunction "101_101") (pintype "bidirectional"))
    )
    (net (code "63") (name "OUT8_P") (class "Default")
      (node (ref "X-SOUTH") (pin "99") (pinfunction "99_99") (pintype "bidirectional"))
    )
    (net (code "64") (name "OUT9_N") (class "Default")
      (node (ref "X-SOUTH") (pin "95") (pinfunction "95_95") (pintype "bidirectional"))
      (node (ref "X-WEST") (pin "40") (pinfunction "40_40") (pintype "bidirectional"))
    )
    (net (code "65") (name "OUT9_P") (class "Default")
      (node (ref "X-SOUTH") (pin "93") (pinfunction "93_93") (pintype "bidirectional"))
      (node (ref "X-WEST") (pin "42") (pinfunction "42_42") (pintype "bidirectional"))
    )
    (net (code "66") (name "OUT10_N") (class "Default")
      (node (ref "X-SOUTH") (pin "94") (pinfunction "94_94") (pintype "bidirectional"))
    )
    (net (code "67") (name "OUT10_P") (class "Default")
      (node (ref "X-SOUTH") (pin "92") (pinfunction "92_92") (pintype "bidirectional"))
    )
    (net (code "68") (name "OUT11_N") (class "Default")
      (node (ref "X-SOUTH") (pin "100") (pinfunction "100_100") (pintype "bidirectional"))
      (node (ref "X-WEST") (pin "39") (pinfunction "39_39") (pintype "bidirectional"))
    )
    (net (code "69") (name "OUT11_P") (class "Default")
      (node (ref "X-SOUTH") (pin "98") (pinfunction "98_98") (pintype "bidirectional"))
      (node (ref "X-WEST") (pin "41") (pinfunction "41_41") (pintype "bidirectional"))
    )
    (net (code "70") (name "OUT12_N") (class "Default")
      (node (ref "X-SOUTH") (pin "89") (pinfunction "89_89") (pintype "bidirectional"))
    )
    (net (code "71") (name "OUT12_P") (class "Default")
      (node (ref "X-SOUTH") (pin "87") (pinfunction "87_87") (pintype "bidirectional"))
    )
    (net (code "72") (name "OUT13_N") (class "Default")
      (node (ref "X-SOUTH") (pin "83") (pinfunction "83_83") (pintype "bidirectional"))
      (node (ref "X-WEST") (pin "46") (pinfunction "46_46") (pintype "bidirectional"))
    )
    (net (code "73") (name "OUT13_P") (class "Default")
      (node (ref "X-SOUTH") (pin "81") (pinfunction "81_81") (pintype "bidirectional"))
      (node (ref "X-WEST") (pin "48") (pinfunction "48_48") (pintype "bidirectional"))
    )
    (net (code "74") (name "OUT14_N") (class "Default")
      (node (ref "X-SOUTH") (pin "88") (pinfunction "88_88") (pintype "bidirectional"))
    )
    (net (code "75") (name "OUT14_P") (class "Default")
      (node (ref "X-SOUTH") (pin "86") (pinfunction "86_86") (pintype "bidirectional"))
    )
    (net (code "76") (name "OUT15_N") (class "Default")
      (node (ref "X-EAST") (pin "54") (pinfunction "54_54") (pintype "bidirectional"))
      (node (ref "X-SOUTH") (pin "82") (pinfunction "82_82") (pintype "bidirectional"))
    )
    (net (code "77") (name "OUT15_P") (class "Default")
      (node (ref "X-EAST") (pin "56") (pinfunction "56_56") (pintype "bidirectional"))
      (node (ref "X-SOUTH") (pin "80") (pinfunction "80_80") (pintype "bidirectional"))
    )
    (net (code "78") (name "OUT16_N") (class "Default")
      (node (ref "X-SOUTH") (pin "77") (pinfunction "77_77") (pintype "bidirectional"))
    )
    (net (code "79") (name "OUT16_P") (class "Default")
      (node (ref "X-SOUTH") (pin "75") (pinfunction "75_75") (pintype "bidirectional"))
    )
    (net (code "80") (name "OUT17_N") (class "Default")
      (node (ref "X-EAST") (pin "53") (pinfunction "53_53") (pintype "bidirectional"))
      (node (ref "X-SOUTH") (pin "76") (pinfunction "76_76") (pintype "bidirectional"))
    )
    (net (code "81") (name "OUT17_P") (class "Default")
      (node (ref "X-EAST") (pin "55") (pinfunction "55_55") (pintype "bidirectional"))
      (node (ref "X-SOUTH") (pin "74") (pinfunction "74_74") (pintype "bidirectional"))
    )
    (net (code "82") (name "OUT18_N") (class "Default")
      (node (ref "X-SOUTH") (pin "71") (pinfunction "71_71") (pintype "bidirectional"))
    )
    (net (code "83") (name "OUT18_P") (class "Default")
      (node (ref "X-SOUTH") (pin "69") (pinfunction "69_69") (pintype "bidirectional"))
    )
    (net (code "84") (name "OUT19_N") (class "Default")
      (node (ref "X-EAST") (pin "60") (pinfunction "60_60") (pintype "bidirectional"))
      (node (ref "X-SOUTH") (pin "65") (pinfunction "65_65") (pintype "bidirectional"))
    )
    (net (code "85") (name "OUT19_P") (class "Default")
      (node (ref "X-EAST") (pin "62") (pinfunction "62_62") (pintype "bidirectional"))
      (node (ref "X-SOUTH") (pin "63") (pinfunction "63_63") (pintype "bidirectional"))
    )
    (net (code "86") (name "OUT20_N") (class "Default")
      (node (ref "X-SOUTH") (pin "70") (pinfunction "70_70") (pintype "bidirectional"))
    )
    (net (code "87") (name "OUT20_P") (class "Default")
      (node (ref "X-SOUTH") (pin "68") (pinfunction "68_68") (pintype "bidirectional"))
    )
    (net (code "88") (name "OUT21_N") (class "Default")
      (node (ref "X-EAST") (pin "59") (pinfunction "59_59") (pintype "bidirectional"))
      (node (ref "X-SOUTH") (pin "64") (pinfunction "64_64") (pintype "bidirectional"))
    )
    (net (code "89") (name "OUT21_P") (class "Default")
      (node (ref "X-EAST") (pin "61") (pinfunction "61_61") (pintype "bidirectional"))
      (node (ref "X-SOUTH") (pin "62") (pinfunction "62_62") (pintype "bidirectional"))
    )
    (net (code "90") (name "OUT22_N") (class "Default")
      (node (ref "X-SOUTH") (pin "59") (pinfunction "59_59") (pintype "bidirectional"))
    )
    (net (code "91") (name "OUT22_P") (class "Default")
      (node (ref "X-SOUTH") (pin "57") (pinfunction "57_57") (pintype "bidirectional"))
    )
    (net (code "92") (name "OUT23_N") (class "Default")
      (node (ref "X-EAST") (pin "66") (pinfunction "66_66") (pintype "bidirectional"))
      (node (ref "X-SOUTH") (pin "53") (pinfunction "53_53") (pintype "bidirectional"))
    )
    (net (code "93") (name "OUT23_P") (class "Default")
      (node (ref "X-EAST") (pin "68") (pinfunction "68_68") (pintype "bidirectional"))
      (node (ref "X-SOUTH") (pin "51") (pinfunction "51_51") (pintype "bidirectional"))
    )
    (net (code "94") (name "OUT24_N") (class "Default")
      (node (ref "X-SOUTH") (pin "52") (pinfunction "52_52") (pintype "bidirectional"))
    )
    (net (code "95") (name "OUT24_P") (class "Default")
      (node (ref "X-SOUTH") (pin "50") (pinfunction "50_50") (pintype "bidirectional"))
    )
    (net (code "96") (name "OUT25_N") (class "Default")
      (node (ref "X-EAST") (pin "65") (pinfunction "65_65") (pintype "bidirectional"))
      (node (ref "X-SOUTH") (pin "58") (pinfunction "58_58") (pintype "bidirectional"))
    )
    (net (code "97") (name "OUT25_P") (class "Default")
      (node (ref "X-EAST") (pin "67") (pinfunction "67_67") (pintype "bidirectional"))
      (node (ref "X-SOUTH") (pin "56") (pinfunction "56_56") (pintype "bidirectional"))
    )
    (net (code "98") (name "OUT26_N") (class "Default")
      (node (ref "X-SOUTH") (pin "47") (pinfunction "47_47") (pintype "bidirectional"))
    )
    (net (code "99") (name "OUT26_P") (class "Default")
      (node (ref "X-SOUTH") (pin "45") (pinfunction "45_45") (pintype "bidirectional"))
    )
    (net (code "100") (name "OUT27_N") (class "Default")
      (node (ref "X-EAST") (pin "73") (pinfunction "73_73") (pintype "bidirectional"))
      (node (ref "X-SOUTH") (pin "40") (pinfunction "40_40") (pintype "bidirectional"))
    )
    (net (code "101") (name "OUT27_P") (class "Default")
      (node (ref "X-EAST") (pin "75") (pinfunction "75_75") (pintype "bidirectional"))
      (node (ref "X-SOUTH") (pin "38") (pinfunction "38_38") (pintype "bidirectional"))
    )
    (net (code "102") (name "OUT28_N") (class "Default")
      (node (ref "X-SOUTH") (pin "46") (pinfunction "46_46") (pintype "bidirectional"))
    )
    (net (code "103") (name "OUT28_P") (class "Default")
      (node (ref "X-SOUTH") (pin "44") (pinfunction "44_44") (pintype "bidirectional"))
    )
    (net (code "104") (name "OUT29_N") (class "Default")
      (node (ref "X-EAST") (pin "72") (pinfunction "72_72") (pintype "bidirectional"))
      (node (ref "X-SOUTH") (pin "41") (pinfunction "41_41") (pintype "bidirectional"))
    )
    (net (code "105") (name "OUT29_P") (class "Default")
      (node (ref "X-EAST") (pin "74") (pinfunction "74_74") (pintype "bidirectional"))
      (node (ref "X-SOUTH") (pin "39") (pinfunction "39_39") (pintype "bidirectional"))
    )
    (net (code "106") (name "OUT30_N") (class "Default")
      (node (ref "X-SOUTH") (pin "34") (pinfunction "34_34") (pintype "bidirectional"))
    )
    (net (code "107") (name "OUT30_P") (class "Default")
      (node (ref "X-SOUTH") (pin "32") (pinfunction "32_32") (pintype "bidirectional"))
    )
    (net (code "108") (name "OUT31_N") (class "Default")
      (node (ref "X-EAST") (pin "78") (pinfunction "78_78") (pintype "bidirectional"))
      (node (ref "X-SOUTH") (pin "35") (pinfunction "35_35") (pintype "bidirectional"))
    )
    (net (code "109") (name "OUT31_P") (class "Default")
      (node (ref "X-EAST") (pin "80") (pinfunction "80_80") (pintype "bidirectional"))
      (node (ref "X-SOUTH") (pin "33") (pinfunction "33_33") (pintype "bidirectional"))
    )
    (net (code "110") (name "OUT32_N") (class "Default")
      (node (ref "X-SOUTH") (pin "28") (pinfunction "28_28") (pintype "bidirectional"))
    )
    (net (code "111") (name "OUT32_P") (class "Default")
      (node (ref "X-SOUTH") (pin "26") (pinfunction "26_26") (pintype "bidirectional"))
    )
    (net (code "112") (name "OUT33_N") (class "Default")
      (node (ref "X-NORTH") (pin "20") (pinfunction "20_20") (pintype "bidirectional"))
      (node (ref "X-WEST") (pin "67") (pinfunction "67_67") (pintype "bidirectional"))
    )
    (net (code "113") (name "OUT33_P") (class "Default")
      (node (ref "X-NORTH") (pin "22") (pinfunction "22_22") (pintype "bidirectional"))
      (node (ref "X-WEST") (pin "65") (pinfunction "65_65") (pintype "bidirectional"))
    )
    (net (code "114") (name "OUT34_N") (class "Default")
      (node (ref "X-NORTH") (pin "27") (pinfunction "27_27") (pintype "bidirectional"))
    )
    (net (code "115") (name "OUT34_P") (class "Default")
      (node (ref "X-NORTH") (pin "29") (pinfunction "29_29") (pintype "bidirectional"))
    )
    (net (code "116") (name "OUT35_N") (class "Default")
      (node (ref "X-NORTH") (pin "26") (pinfunction "26_26") (pintype "bidirectional"))
      (node (ref "X-WEST") (pin "61") (pinfunction "61_61") (pintype "bidirectional"))
    )
    (net (code "117") (name "OUT35_P") (class "Default")
      (node (ref "X-NORTH") (pin "28") (pinfunction "28_28") (pintype "bidirectional"))
      (node (ref "X-WEST") (pin "59") (pinfunction "59_59") (pintype "bidirectional"))
    )
    (net (code "118") (name "OUT36_N") (class "Default")
      (node (ref "X-NORTH") (pin "33") (pinfunction "33_33") (pintype "bidirectional"))
    )
    (net (code "119") (name "OUT36_P") (class "Default")
      (node (ref "X-NORTH") (pin "35") (pinfunction "35_35") (pintype "bidirectional"))
    )
    (net (code "120") (name "OUT37_N") (class "Default")
      (node (ref "X-NORTH") (pin "32") (pinfunction "32_32") (pintype "bidirectional"))
      (node (ref "X-WEST") (pin "47") (pinfunction "47_47") (pintype "bidirectional"))
    )
    (net (code "121") (name "OUT37_P") (class "Default")
      (node (ref "X-NORTH") (pin "34") (pinfunction "34_34") (pintype "bidirectional"))
      (node (ref "X-WEST") (pin "45") (pinfunction "45_45") (pintype "bidirectional"))
    )
    (net (code "122") (name "OUT38_N") (class "Default")
      (node (ref "X-NORTH") (pin "38") (pinfunction "38_38") (pintype "bidirectional"))
    )
    (net (code "123") (name "OUT38_P") (class "Default")
      (node (ref "X-NORTH") (pin "40") (pinfunction "40_40") (pintype "bidirectional"))
    )
    (net (code "124") (name "OUT39_N") (class "Default")
      (node (ref "X-NORTH") (pin "39") (pinfunction "39_39") (pintype "bidirectional"))
      (node (ref "X-WEST") (pin "80") (pinfunction "80_80") (pintype "bidirectional"))
    )
    (net (code "125") (name "OUT39_P") (class "Default")
      (node (ref "X-NORTH") (pin "41") (pinfunction "41_41") (pintype "bidirectional"))
      (node (ref "X-WEST") (pin "78") (pinfunction "78_78") (pintype "bidirectional"))
    )
    (net (code "126") (name "OUT40_N") (class "Default")
      (node (ref "X-NORTH") (pin "44") (pinfunction "44_44") (pintype "bidirectional"))
    )
    (net (code "127") (name "OUT40_P") (class "Default")
      (node (ref "X-NORTH") (pin "46") (pinfunction "46_46") (pintype "bidirectional"))
    )
    (net (code "128") (name "OUT41_N") (class "Default")
      (node (ref "X-NORTH") (pin "45") (pinfunction "45_45") (pintype "bidirectional"))
      (node (ref "X-WEST") (pin "74") (pinfunction "74_74") (pintype "bidirectional"))
    )
    (net (code "129") (name "OUT41_P") (class "Default")
      (node (ref "X-NORTH") (pin "47") (pinfunction "47_47") (pintype "bidirectional"))
      (node (ref "X-WEST") (pin "72") (pinfunction "72_72") (pintype "bidirectional"))
    )
    (net (code "130") (name "OUT42_N") (class "Default")
      (node (ref "X-NORTH") (pin "50") (pinfunction "50_50") (pintype "bidirectional"))
    )
    (net (code "131") (name "OUT42_P") (class "Default")
      (node (ref "X-NORTH") (pin "52") (pinfunction "52_52") (pintype "bidirectional"))
    )
    (net (code "132") (name "OUT43_N") (class "Default")
      (node (ref "X-NORTH") (pin "51") (pinfunction "51_51") (pintype "bidirectional"))
      (node (ref "X-WEST") (pin "68") (pinfunction "68_68") (pintype "bidirectional"))
    )
    (net (code "133") (name "OUT43_P") (class "Default")
      (node (ref "X-NORTH") (pin "53") (pinfunction "53_53") (pintype "bidirectional"))
      (node (ref "X-WEST") (pin "66") (pinfunction "66_66") (pintype "bidirectional"))
    )
    (net (code "134") (name "OUT44_N") (class "Default")
      (node (ref "X-NORTH") (pin "56") (pinfunction "56_56") (pintype "bidirectional"))
    )
    (net (code "135") (name "OUT44_P") (class "Default")
      (node (ref "X-NORTH") (pin "58") (pinfunction "58_58") (pintype "bidirectional"))
    )
    (net (code "136") (name "OUT45_N") (class "Default")
      (node (ref "X-NORTH") (pin "57") (pinfunction "57_57") (pintype "bidirectional"))
      (node (ref "X-WEST") (pin "62") (pinfunction "62_62") (pintype "bidirectional"))
    )
    (net (code "137") (name "OUT45_P") (class "Default")
      (node (ref "X-NORTH") (pin "59") (pinfunction "59_59") (pintype "bidirectional"))
      (node (ref "X-WEST") (pin "60") (pinfunction "60_60") (pintype "bidirectional"))
    )
    (net (code "138") (name "OUT46_N") (class "Default")
      (node (ref "X-NORTH") (pin "62") (pinfunction "62_62") (pintype "bidirectional"))
    )
    (net (code "139") (name "OUT46_P") (class "Default")
      (node (ref "X-NORTH") (pin "64") (pinfunction "64_64") (pintype "bidirectional"))
    )
    (net (code "140") (name "OUT47_N") (class "Default")
      (node (ref "X-NORTH") (pin "63") (pinfunction "63_63") (pintype "bidirectional"))
      (node (ref "X-WEST") (pin "56") (pinfunction "56_56") (pintype "bidirectional"))
    )
    (net (code "141") (name "OUT47_P") (class "Default")
      (node (ref "X-NORTH") (pin "65") (pinfunction "65_65") (pintype "bidirectional"))
      (node (ref "X-WEST") (pin "54") (pinfunction "54_54") (pintype "bidirectional"))
    )
    (net (code "142") (name "OUT48_N") (class "Default")
      (node (ref "X-NORTH") (pin "68") (pinfunction "68_68") (pintype "bidirectional"))
    )
    (net (code "143") (name "OUT48_P") (class "Default")
      (node (ref "X-NORTH") (pin "70") (pinfunction "70_70") (pintype "bidirectional"))
    )
    (net (code "144") (name "OUT49_N") (class "Default")
      (node (ref "X-EAST") (pin "48") (pinfunction "48_48") (pintype "bidirectional"))
      (node (ref "X-NORTH") (pin "74") (pinfunction "74_74") (pintype "bidirectional"))
    )
    (net (code "145") (name "OUT49_P") (class "Default")
      (node (ref "X-EAST") (pin "46") (pinfunction "46_46") (pintype "bidirectional"))
      (node (ref "X-NORTH") (pin "76") (pinfunction "76_76") (pintype "bidirectional"))
    )
    (net (code "146") (name "OUT50_N") (class "Default")
      (node (ref "X-NORTH") (pin "69") (pinfunction "69_69") (pintype "bidirectional"))
    )
    (net (code "147") (name "OUT50_P") (class "Default")
      (node (ref "X-NORTH") (pin "71") (pinfunction "71_71") (pintype "bidirectional"))
    )
    (net (code "148") (name "OUT51_N") (class "Default")
      (node (ref "X-EAST") (pin "42") (pinfunction "42_42") (pintype "bidirectional"))
      (node (ref "X-NORTH") (pin "80") (pinfunction "80_80") (pintype "bidirectional"))
    )
    (net (code "149") (name "OUT51_P") (class "Default")
      (node (ref "X-EAST") (pin "40") (pinfunction "40_40") (pintype "bidirectional"))
      (node (ref "X-NORTH") (pin "82") (pinfunction "82_82") (pintype "bidirectional"))
    )
    (net (code "150") (name "OUT52_N") (class "Default")
      (node (ref "X-NORTH") (pin "75") (pinfunction "75_75") (pintype "bidirectional"))
    )
    (net (code "151") (name "OUT52_P") (class "Default")
      (node (ref "X-NORTH") (pin "77") (pinfunction "77_77") (pintype "bidirectional"))
    )
    (net (code "152") (name "OUT53_N") (class "Default")
      (node (ref "X-EAST") (pin "47") (pinfunction "47_47") (pintype "bidirectional"))
      (node (ref "X-NORTH") (pin "86") (pinfunction "86_86") (pintype "bidirectional"))
    )
    (net (code "153") (name "OUT53_P") (class "Default")
      (node (ref "X-EAST") (pin "45") (pinfunction "45_45") (pintype "bidirectional"))
      (node (ref "X-NORTH") (pin "88") (pinfunction "88_88") (pintype "bidirectional"))
    )
    (net (code "154") (name "OUT54_N") (class "Default")
      (node (ref "X-NORTH") (pin "81") (pinfunction "81_81") (pintype "bidirectional"))
    )
    (net (code "155") (name "OUT54_P") (class "Default")
      (node (ref "X-NORTH") (pin "83") (pinfunction "83_83") (pintype "bidirectional"))
    )
    (net (code "156") (name "OUT55_N") (class "Default")
      (node (ref "X-EAST") (pin "41") (pinfunction "41_41") (pintype "bidirectional"))
      (node (ref "X-NORTH") (pin "92") (pinfunction "92_92") (pintype "bidirectional"))
    )
    (net (code "157") (name "OUT55_P") (class "Default")
      (node (ref "X-EAST") (pin "39") (pinfunction "39_39") (pintype "bidirectional"))
      (node (ref "X-NORTH") (pin "94") (pinfunction "94_94") (pintype "bidirectional"))
    )
    (net (code "158") (name "OUT56_N") (class "Default")
      (node (ref "X-NORTH") (pin "87") (pinfunction "87_87") (pintype "bidirectional"))
    )
    (net (code "159") (name "OUT56_P") (class "Default")
      (node (ref "X-NORTH") (pin "89") (pinfunction "89_89") (pintype "bidirectional"))
    )
    (net (code "160") (name "OUT57_N") (class "Default")
      (node (ref "X-EAST") (pin "35") (pinfunction "35_35") (pintype "bidirectional"))
      (node (ref "X-NORTH") (pin "98") (pinfunction "98_98") (pintype "bidirectional"))
    )
    (net (code "161") (name "OUT57_P") (class "Default")
      (node (ref "X-EAST") (pin "33") (pinfunction "33_33") (pintype "bidirectional"))
      (node (ref "X-NORTH") (pin "100") (pinfunction "100_100") (pintype "bidirectional"))
    )
    (net (code "162") (name "OUT58_N") (class "Default")
      (node (ref "X-NORTH") (pin "93") (pinfunction "93_93") (pintype "bidirectional"))
    )
    (net (code "163") (name "OUT58_P") (class "Default")
      (node (ref "X-NORTH") (pin "95") (pinfunction "95_95") (pintype "bidirectional"))
    )
    (net (code "164") (name "OUT59_N") (class "Default")
      (node (ref "X-EAST") (pin "27") (pinfunction "27_27") (pintype "bidirectional"))
      (node (ref "X-NORTH") (pin "104") (pinfunction "104_104") (pintype "bidirectional"))
    )
    (net (code "165") (name "OUT59_P") (class "Default")
      (node (ref "X-EAST") (pin "25") (pinfunction "25_25") (pintype "bidirectional"))
      (node (ref "X-NORTH") (pin "106") (pinfunction "106_106") (pintype "bidirectional"))
    )
    (net (code "166") (name "OUT60_N") (class "Default")
      (node (ref "X-NORTH") (pin "110") (pinfunction "110_110") (pintype "bidirectional"))
    )
    (net (code "167") (name "OUT60_P") (class "Default")
      (node (ref "X-NORTH") (pin "112") (pinfunction "112_112") (pintype "bidirectional"))
    )
    (net (code "168") (name "OUT61_N") (class "Default")
      (node (ref "X-EAST") (pin "36") (pinfunction "36_36") (pintype "bidirectional"))
      (node (ref "X-NORTH") (pin "99") (pinfunction "99_99") (pintype "bidirectional"))
    )
    (net (code "169") (name "OUT61_P") (class "Default")
      (node (ref "X-EAST") (pin "34") (pinfunction "34_34") (pintype "bidirectional"))
      (node (ref "X-NORTH") (pin "101") (pinfunction "101_101") (pintype "bidirectional"))
    )
    (net (code "170") (name "OUT62_N") (class "Default")
      (node (ref "X-NORTH") (pin "116") (pinfunction "116_116") (pintype "bidirectional"))
    )
    (net (code "171") (name "OUT62_P") (class "Default")
      (node (ref "X-NORTH") (pin "118") (pinfunction "118_118") (pintype "bidirectional"))
    )
    (net (code "172") (name "OUT63_N") (class "Default")
      (node (ref "X-EAST") (pin "30") (pinfunction "30_30") (pintype "bidirectional"))
      (node (ref "X-NORTH") (pin "105") (pinfunction "105_105") (pintype "bidirectional"))
    )
    (net (code "173") (name "OUT63_P") (class "Default")
      (node (ref "X-EAST") (pin "28") (pinfunction "28_28") (pintype "bidirectional"))
      (node (ref "X-NORTH") (pin "107") (pinfunction "107_107") (pintype "bidirectional"))
    )
    (net (code "174") (name "OUT64_N") (class "Default")
      (node (ref "X-NORTH") (pin "111") (pinfunction "111_111") (pintype "bidirectional"))
    )
    (net (code "175") (name "OUT64_P") (class "Default")
      (node (ref "X-NORTH") (pin "113") (pinfunction "113_113") (pintype "bidirectional"))
    )
    (net (code "176") (name "OUTCLK_N") (class "Default")
      (node (ref "X-NORTH") (pin "15") (pinfunction "15_15") (pintype "bidirectional"))
      (node (ref "X-WEST") (pin "53") (pinfunction "53_53") (pintype "bidirectional"))
    )
    (net (code "177") (name "OUTCLK_P") (class "Default")
      (node (ref "X-NORTH") (pin "17") (pinfunction "17_17") (pintype "bidirectional"))
      (node (ref "X-WEST") (pin "55") (pinfunction "55_55") (pintype "bidirectional"))
    )
    (net (code "178") (name "OUTCTR_N") (class "Default")
      (node (ref "X-SOUTH") (pin "125") (pinfunction "125_125") (pintype "bidirectional"))
      (node (ref "X-WEST") (pin "22") (pinfunction "22_22") (pintype "bidirectional"))
    )
    (net (code "179") (name "OUTCTR_P") (class "Default")
      (node (ref "X-SOUTH") (pin "123") (pinfunction "123_123") (pintype "bidirectional"))
      (node (ref "X-WEST") (pin "24") (pinfunction "24_24") (pintype "bidirectional"))
    )
    (net (code "180") (name "RES1") (class "Default")
      (node (ref "X-WEST") (pin "79") (pinfunction "79_79") (pintype "bidirectional"))
    )
    (net (code "181") (name "RES2") (class "Default")
      (node (ref "X-WEST") (pin "81") (pinfunction "81_81") (pintype "bidirectional"))
    )
    (net (code "182") (name "RES3") (class "Default")
      (node (ref "X-WEST") (pin "83") (pinfunction "83_83") (pintype "bidirectional"))
    )
    (net (code "183") (name "RES4") (class "Default")
      (node (ref "X-EAST") (pin "79") (pinfunction "79_79") (pintype "bidirectional"))
    )
    (net (code "184") (name "RES5") (class "Default")
      (node (ref "X-EAST") (pin "81") (pinfunction "81_81") (pintype "bidirectional"))
    )
    (net (code "185") (name "RES6") (class "Default")
      (node (ref "X-EAST") (pin "83") (pinfunction "83_83") (pintype "bidirectional"))
    )
    (net (code "186") (name "S00_N") (class "Default")
      (node (ref "X-SOUTH") (pin "16") (pinfunction "16_16") (pintype "bidirectional"))
    )
    (net (code "187") (name "S00_P") (class "Default")
      (node (ref "X-SOUTH") (pin "14") (pinfunction "14_14") (pintype "bidirectional"))
    )
    (net (code "188") (name "S01_N") (class "Default")
      (node (ref "X-SOUTH") (pin "17") (pinfunction "17_17") (pintype "bidirectional"))
    )
    (net (code "189") (name "S01_P") (class "Default")
      (node (ref "X-SOUTH") (pin "15") (pinfunction "15_15") (pintype "bidirectional"))
    )
    (net (code "190") (name "S02_N") (class "Default")
      (node (ref "X-SOUTH") (pin "22") (pinfunction "22_22") (pintype "bidirectional"))
    )
    (net (code "191") (name "S02_P") (class "Default")
      (node (ref "X-SOUTH") (pin "20") (pinfunction "20_20") (pintype "bidirectional"))
    )
    (net (code "192") (name "S03_N") (class "Default")
      (node (ref "X-SOUTH") (pin "23") (pinfunction "23_23") (pintype "bidirectional"))
    )
    (net (code "193") (name "S03_P") (class "Default")
      (node (ref "X-SOUTH") (pin "21") (pinfunction "21_21") (pintype "bidirectional"))
    )
    (net (code "194") (name "S05_N") (class "Default")
      (node (ref "X-SOUTH") (pin "29") (pinfunction "29_29") (pintype "bidirectional"))
    )
    (net (code "195") (name "S05_P") (class "Default")
      (node (ref "X-SOUTH") (pin "27") (pinfunction "27_27") (pintype "bidirectional"))
    )
    (net (code "196") (name "S38_N") (class "Default")
      (node (ref "X-SOUTH") (pin "130") (pinfunction "130_130") (pintype "bidirectional"))
    )
    (net (code "197") (name "S38_P") (class "Default")
      (node (ref "X-SOUTH") (pin "128") (pinfunction "128_128") (pintype "bidirectional"))
    )
    (net (code "198") (name "S39_N") (class "Default")
      (node (ref "X-SOUTH") (pin "131") (pinfunction "131_131") (pintype "bidirectional"))
    )
    (net (code "199") (name "S39_P") (class "Default")
      (node (ref "X-SOUTH") (pin "129") (pinfunction "129_129") (pintype "bidirectional"))
    )
    (net (code "200") (name "SYS_RES_N") (class "Default")
      (node (ref "X-EAST") (pin "22") (pinfunction "22_22") (pintype "bidirectional"))
      (node (ref "X-NORTH") (pin "125") (pinfunction "125_125") (pintype "bidirectional"))
    )
    (net (code "201") (name "S_CHK_EN") (class "Default")
      (node (ref "X-EAST") (pin "94") (pinfunction "94_94") (pintype "bidirectional"))
      (node (ref "X-SOUTH") (pin "8") (pinfunction "8_8") (pintype "bidirectional"))
    )
    (net (code "202") (name "S_CHK_V") (class "Default")
      (node (ref "X-EAST") (pin "92") (pinfunction "92_92") (pintype "bidirectional"))
      (node (ref "X-SOUTH") (pin "10") (pinfunction "10_10") (pintype "bidirectional"))
    )
    (net (code "203") (name "S_I2C_EN") (class "Default")
      (node (ref "X-SOUTH") (pin "137") (pinfunction "137_137") (pintype "bidirectional"))
      (node (ref "X-WEST") (pin "7") (pinfunction "7_7") (pintype "bidirectional"))
    )
    (net (code "204") (name "S_I2C_V") (class "Default")
      (node (ref "X-SOUTH") (pin "135") (pinfunction "135_135") (pintype "bidirectional"))
      (node (ref "X-WEST") (pin "9") (pinfunction "9_9") (pintype "bidirectional"))
    )
    (net (code "205") (name "S_SCK") (class "Default")
      (node (ref "X-SOUTH") (pin "144") (pinfunction "144_144") (pintype "bidirectional"))
      (node (ref "X-WEST") (pin "2") (pinfunction "2_2") (pintype "bidirectional"))
    )
    (net (code "206") (name "S_SCL") (class "Default")
      (node (ref "X-SOUTH") (pin "143") (pinfunction "143_143") (pintype "bidirectional"))
      (node (ref "X-WEST") (pin "1") (pinfunction "1_1") (pintype "bidirectional"))
    )
    (net (code "207") (name "S_SDA") (class "Default")
      (node (ref "X-SOUTH") (pin "141") (pinfunction "141_141") (pintype "bidirectional"))
      (node (ref "X-WEST") (pin "3") (pinfunction "3_3") (pintype "bidirectional"))
    )
    (net (code "208") (name "S_SDI") (class "Default")
      (node (ref "X-SOUTH") (pin "140") (pinfunction "140_140") (pintype "bidirectional"))
      (node (ref "X-WEST") (pin "6") (pinfunction "6_6") (pintype "bidirectional"))
    )
    (net (code "209") (name "S_SDO") (class "Default")
      (node (ref "X-SOUTH") (pin "142") (pinfunction "142_142") (pintype "bidirectional"))
      (node (ref "X-WEST") (pin "4") (pinfunction "4_4") (pintype "bidirectional"))
    )
    (net (code "210") (name "S_SPI_EN") (class "Default")
      (node (ref "X-SOUTH") (pin "136") (pinfunction "136_136") (pintype "bidirectional"))
      (node (ref "X-WEST") (pin "8") (pinfunction "8_8") (pintype "bidirectional"))
    )
    (net (code "211") (name "S_SPI_V") (class "Default")
      (node (ref "X-SOUTH") (pin "134") (pinfunction "134_134") (pintype "bidirectional"))
      (node (ref "X-WEST") (pin "10") (pinfunction "10_10") (pintype "bidirectional"))
    )
    (net (code "212") (name "S_VE") (class "Default")
      (node (ref "C7") (pin "1") (pinfunction "1_1") (pintype "passive"))
      (node (ref "SE") (pin "1") (pinfunction "1_1") (pintype "passive"))
      (node (ref "X-SOUTH") (pin "13") (pinfunction "13_13") (pintype "bidirectional"))
      (node (ref "X-SOUTH") (pin "19") (pinfunction "19_19") (pintype "bidirectional"))
      (node (ref "X-SOUTH") (pin "31") (pinfunction "31_31") (pintype "bidirectional"))
      (node (ref "X-SOUTH") (pin "37") (pinfunction "37_37") (pintype "bidirectional"))
    )
    (net (code "213") (name "S_VE_CV") (class "Default")
      (node (ref "X-EAST") (pin "100") (pinfunction "100_100") (pintype "bidirectional"))
      (node (ref "X-SOUTH") (pin "2") (pinfunction "2_2") (pintype "bidirectional"))
    )
    (net (code "214") (name "S_VE_OV") (class "Default")
      (node (ref "X-EAST") (pin "99") (pinfunction "99_99") (pintype "bidirectional"))
      (node (ref "X-SOUTH") (pin "1") (pinfunction "1_1") (pintype "bidirectional"))
    )
    (net (code "215") (name "S_VE_RS") (class "Default")
      (node (ref "X-EAST") (pin "84") (pinfunction "84_84") (pintype "bidirectional"))
      (node (ref "X-SOUTH") (pin "25") (pinfunction "25_25") (pintype "bidirectional"))
    )
    (net (code "216") (name "S_VE_UV") (class "Default")
      (node (ref "X-EAST") (pin "89") (pinfunction "89_89") (pintype "bidirectional"))
      (node (ref "X-SOUTH") (pin "7") (pinfunction "7_7") (pintype "bidirectional"))
    )
    (net (code "217") (name "S_VS") (class "Default")
      (node (ref "C6") (pin "1") (pinfunction "1_1") (pintype "passive"))
      (node (ref "SW") (pin "1") (pinfunction "1_1") (pintype "passive"))
      (node (ref "X-SOUTH") (pin "49") (pinfunction "49_49") (pintype "bidirectional"))
      (node (ref "X-SOUTH") (pin "55") (pinfunction "55_55") (pintype "bidirectional"))
      (node (ref "X-SOUTH") (pin "61") (pinfunction "61_61") (pintype "bidirectional"))
      (node (ref "X-SOUTH") (pin "67") (pinfunction "67_67") (pintype "bidirectional"))
      (node (ref "X-SOUTH") (pin "79") (pinfunction "79_79") (pintype "bidirectional"))
      (node (ref "X-SOUTH") (pin "85") (pinfunction "85_85") (pintype "bidirectional"))
      (node (ref "X-SOUTH") (pin "91") (pinfunction "91_91") (pintype "bidirectional"))
      (node (ref "X-SOUTH") (pin "97") (pinfunction "97_97") (pintype "bidirectional"))
    )
    (net (code "218") (name "S_VS_CV") (class "Default")
      (node (ref "X-EAST") (pin "98") (pinfunction "98_98") (pintype "bidirectional"))
      (node (ref "X-SOUTH") (pin "4") (pinfunction "4_4") (pintype "bidirectional"))
    )
    (net (code "219") (name "S_VS_OV") (class "Default")
      (node (ref "X-EAST") (pin "97") (pinfunction "97_97") (pintype "bidirectional"))
      (node (ref "X-SOUTH") (pin "3") (pinfunction "3_3") (pintype "bidirectional"))
    )
    (net (code "220") (name "S_VS_RS") (class "Default")
      (node (ref "X-EAST") (pin "86") (pinfunction "86_86") (pintype "bidirectional"))
      (node (ref "X-SOUTH") (pin "73") (pinfunction "73_73") (pintype "bidirectional"))
    )
    (net (code "221") (name "S_VS_UV") (class "Default")
      (node (ref "X-EAST") (pin "87") (pinfunction "87_87") (pintype "bidirectional"))
      (node (ref "X-SOUTH") (pin "9") (pinfunction "9_9") (pintype "bidirectional"))
    )
    (net (code "222") (name "S_VW") (class "Default")
      (node (ref "C2") (pin "1") (pinfunction "1_1") (pintype "passive"))
      (node (ref "SW") (pin "2") (pinfunction "2_2") (pintype "passive"))
      (node (ref "X-SOUTH") (pin "109") (pinfunction "109_109") (pintype "bidirectional"))
      (node (ref "X-SOUTH") (pin "115") (pinfunction "115_115") (pintype "bidirectional"))
      (node (ref "X-SOUTH") (pin "127") (pinfunction "127_127") (pintype "bidirectional"))
      (node (ref "X-SOUTH") (pin "133") (pinfunction "133_133") (pintype "bidirectional"))
    )
    (net (code "223") (name "S_VW_CV") (class "Default")
      (node (ref "X-EAST") (pin "96") (pinfunction "96_96") (pintype "bidirectional"))
      (node (ref "X-SOUTH") (pin "6") (pinfunction "6_6") (pintype "bidirectional"))
    )
    (net (code "224") (name "S_VW_OV") (class "Default")
      (node (ref "X-EAST") (pin "95") (pinfunction "95_95") (pintype "bidirectional"))
      (node (ref "X-SOUTH") (pin "5") (pinfunction "5_5") (pintype "bidirectional"))
    )
    (net (code "225") (name "S_VW_RS") (class "Default")
      (node (ref "X-EAST") (pin "88") (pinfunction "88_88") (pintype "bidirectional"))
      (node (ref "X-SOUTH") (pin "121") (pinfunction "121_121") (pintype "bidirectional"))
    )
    (net (code "226") (name "S_VW_UV") (class "Default")
      (node (ref "X-EAST") (pin "85") (pinfunction "85_85") (pintype "bidirectional"))
      (node (ref "X-SOUTH") (pin "11") (pinfunction "11_11") (pintype "bidirectional"))
    )
    (net (code "227") (name "TCK") (class "Default")
      (node (ref "X-WEST") (pin "12") (pinfunction "12_12") (pintype "bidirectional"))
    )
    (net (code "228") (name "TDI") (class "Default")
      (node (ref "X-WEST") (pin "16") (pinfunction "16_16") (pintype "bidirectional"))
    )
    (net (code "229") (name "TDIG1") (class "Default")
      (node (ref "X-EAST") (pin "18") (pinfunction "18_18") (pintype "bidirectional"))
      (node (ref "X-NORTH") (pin "123") (pinfunction "123_123") (pintype "bidirectional"))
    )
    (net (code "230") (name "TDIG2") (class "Default")
      (node (ref "X-NORTH") (pin "130") (pinfunction "130_130") (pintype "bidirectional"))
    )
    (net (code "231") (name "TDO") (class "Default")
      (node (ref "X-WEST") (pin "18") (pinfunction "18_18") (pintype "bidirectional"))
    )
    (net (code "232") (name "TMS") (class "Default")
      (node (ref "X-WEST") (pin "14") (pinfunction "14_14") (pintype "bidirectional"))
    )
    (net (code "233") (name "TP9") (class "Default")
      (node (ref "X-NORTH") (pin "119") (pinfunction "119_119") (pintype "bidirectional"))
    )
    (net (code "234") (name "T_EXP1") (class "Default")
      (node (ref "X-EAST") (pin "12") (pinfunction "12_12") (pintype "bidirectional"))
      (node (ref "X-NORTH") (pin "131") (pinfunction "131_131") (pintype "bidirectional"))
    )
    (net (code "235") (name "T_EXP2") (class "Default")
      (node (ref "X-EAST") (pin "16") (pinfunction "16_16") (pintype "bidirectional"))
      (node (ref "X-NORTH") (pin "117") (pinfunction "117_117") (pintype "bidirectional"))
    )
    (net (code "236") (name "W_EN") (class "Default")
      (node (ref "X-WEST") (pin "19") (pinfunction "19_19") (pintype "bidirectional"))
    )
    (net (code "237") (name "W_I2C_EN") (class "Default")
      (node (ref "X-WEST") (pin "13") (pinfunction "13_13") (pintype "bidirectional"))
    )
    (net (code "238") (name "W_I2C_V") (class "Default")
      (node (ref "X-WEST") (pin "11") (pinfunction "11_11") (pintype "bidirectional"))
    )
    (net (code "239") (name "W_SCL") (class "Default")
      (node (ref "X-WEST") (pin "15") (pinfunction "15_15") (pintype "bidirectional"))
    )
    (net (code "240") (name "W_SDA") (class "Default")
      (node (ref "X-WEST") (pin "17") (pinfunction "17_17") (pintype "bidirectional"))
    )
    (net (code "241") (name "W_VW") (class "Default")
      (node (ref "C8") (pin "1") (pinfunction "1_1") (pintype "passive"))
      (node (ref "NW") (pin "2") (pinfunction "2_2") (pintype "passive"))
    )
    (net (code "242") (name "W_VW_CV") (class "Default")
      (node (ref "X-WEST") (pin "90") (pinfunction "90_90") (pintype "bidirectional"))
    )
    (net (code "243") (name "W_VW_OV") (class "Default")
      (node (ref "X-WEST") (pin "93") (pinfunction "93_93") (pintype "bidirectional"))
    )
    (net (code "244") (name "W_VW_UV") (class "Default")
      (node (ref "X-WEST") (pin "91") (pinfunction "91_91") (pintype "bidirectional"))
    )
    (net (code "245") (name "unconnected-(X-EAST-PadM1)") (class "Default")
      (node (ref "X-EAST") (pin "M1") (pinfunction "M1_M1") (pintype "bidirectional"))
    )
    (net (code "246") (name "unconnected-(X-EAST-PadM2)") (class "Default")
      (node (ref "X-EAST") (pin "M2") (pinfunction "M2_M2") (pintype "bidirectional"))
    )
    (net (code "247") (name "unconnected-(X-NORTH-PadM1)") (class "Default")
      (node (ref "X-NORTH") (pin "M1") (pinfunction "M1_M1") (pintype "bidirectional"))
    )
    (net (code "248") (name "unconnected-(X-NORTH-PadM2)") (class "Default")
      (node (ref "X-NORTH") (pin "M2") (pinfunction "M2_M2") (pintype "bidirectional"))
    )
    (net (code "249") (name "unconnected-(X-SOUTH-PadM1)") (class "Default")
      (node (ref "X-SOUTH") (pin "M1") (pinfunction "M1_M1") (pintype "bidirectional"))
    )
    (net (code "250") (name "unconnected-(X-SOUTH-PadM2)") (class "Default")
      (node (ref "X-SOUTH") (pin "M2") (pinfunction "M2_M2") (pintype "bidirectional"))
    )
    (net (code "251") (name "unconnected-(X-WEST-PadM1)") (class "Default")
      (node (ref "X-WEST") (pin "M1") (pinfunction "M1_M1") (pintype "bidirectional"))
    )
    (net (code "252") (name "unconnected-(X-WEST-PadM2)") (class "Default")
      (node (ref "X-WEST") (pin "M2") (pinfunction "M2_M2") (pintype "bidirectional"))
    )
  )
)
